# FPGA_IO.net
KiCad netlist of a schematic drawn in Altium Designer
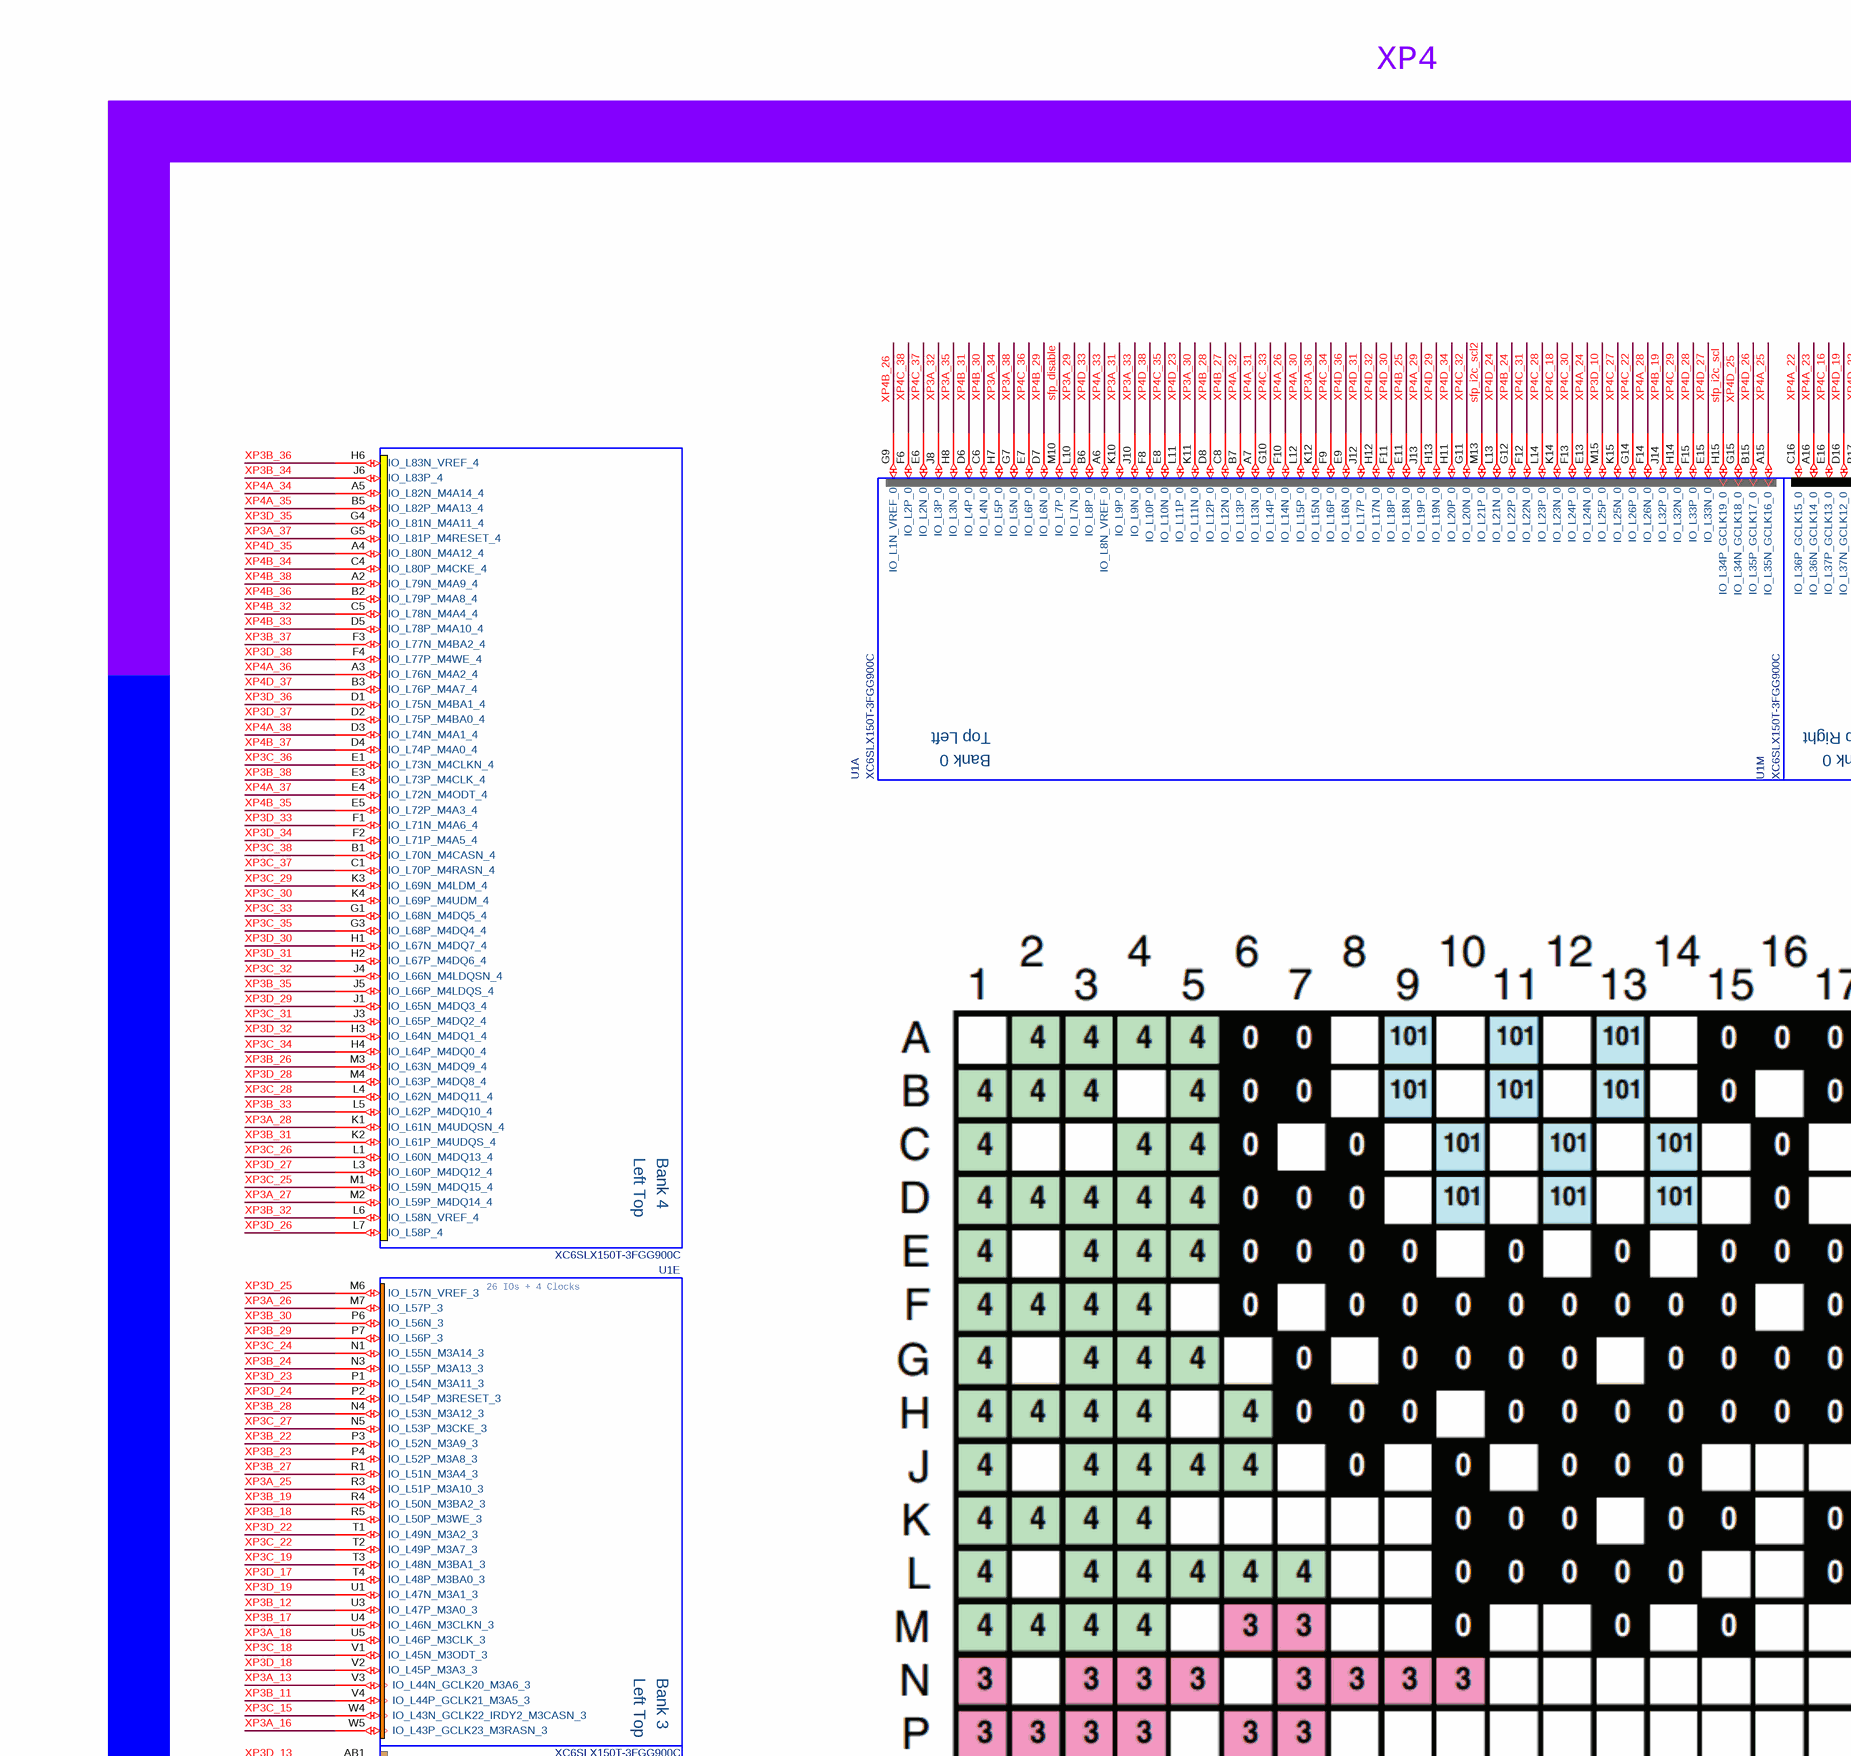
[diagram p0: FPGA_IO.SchDoc, top left]
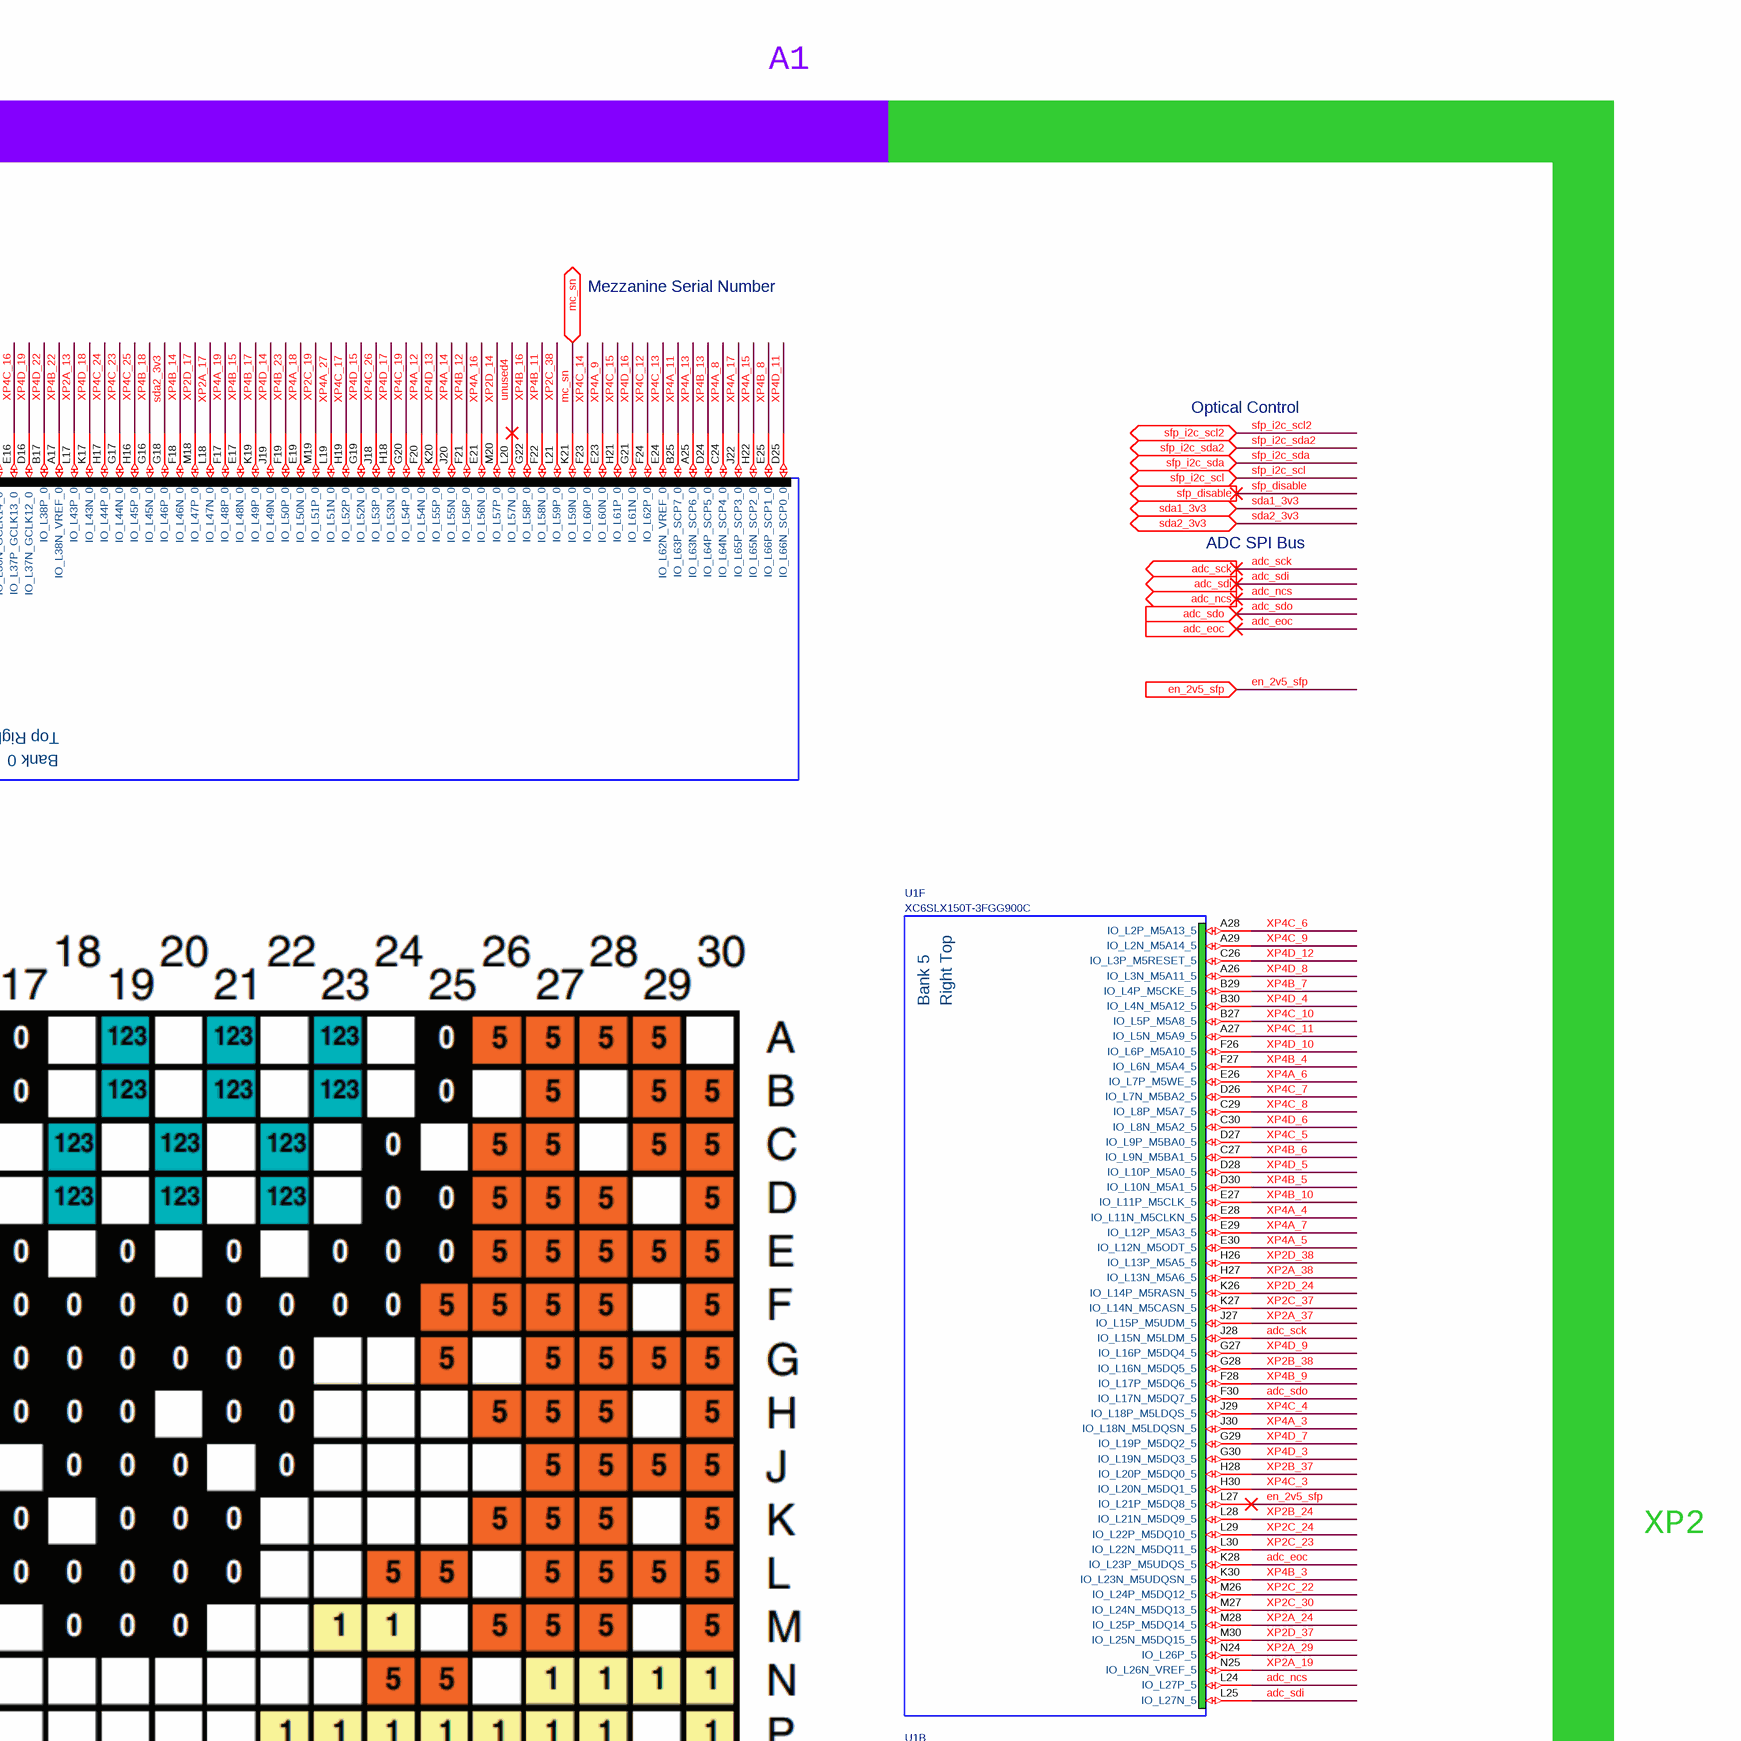
[diagram p1: FPGA_IO.SchDoc, top right]
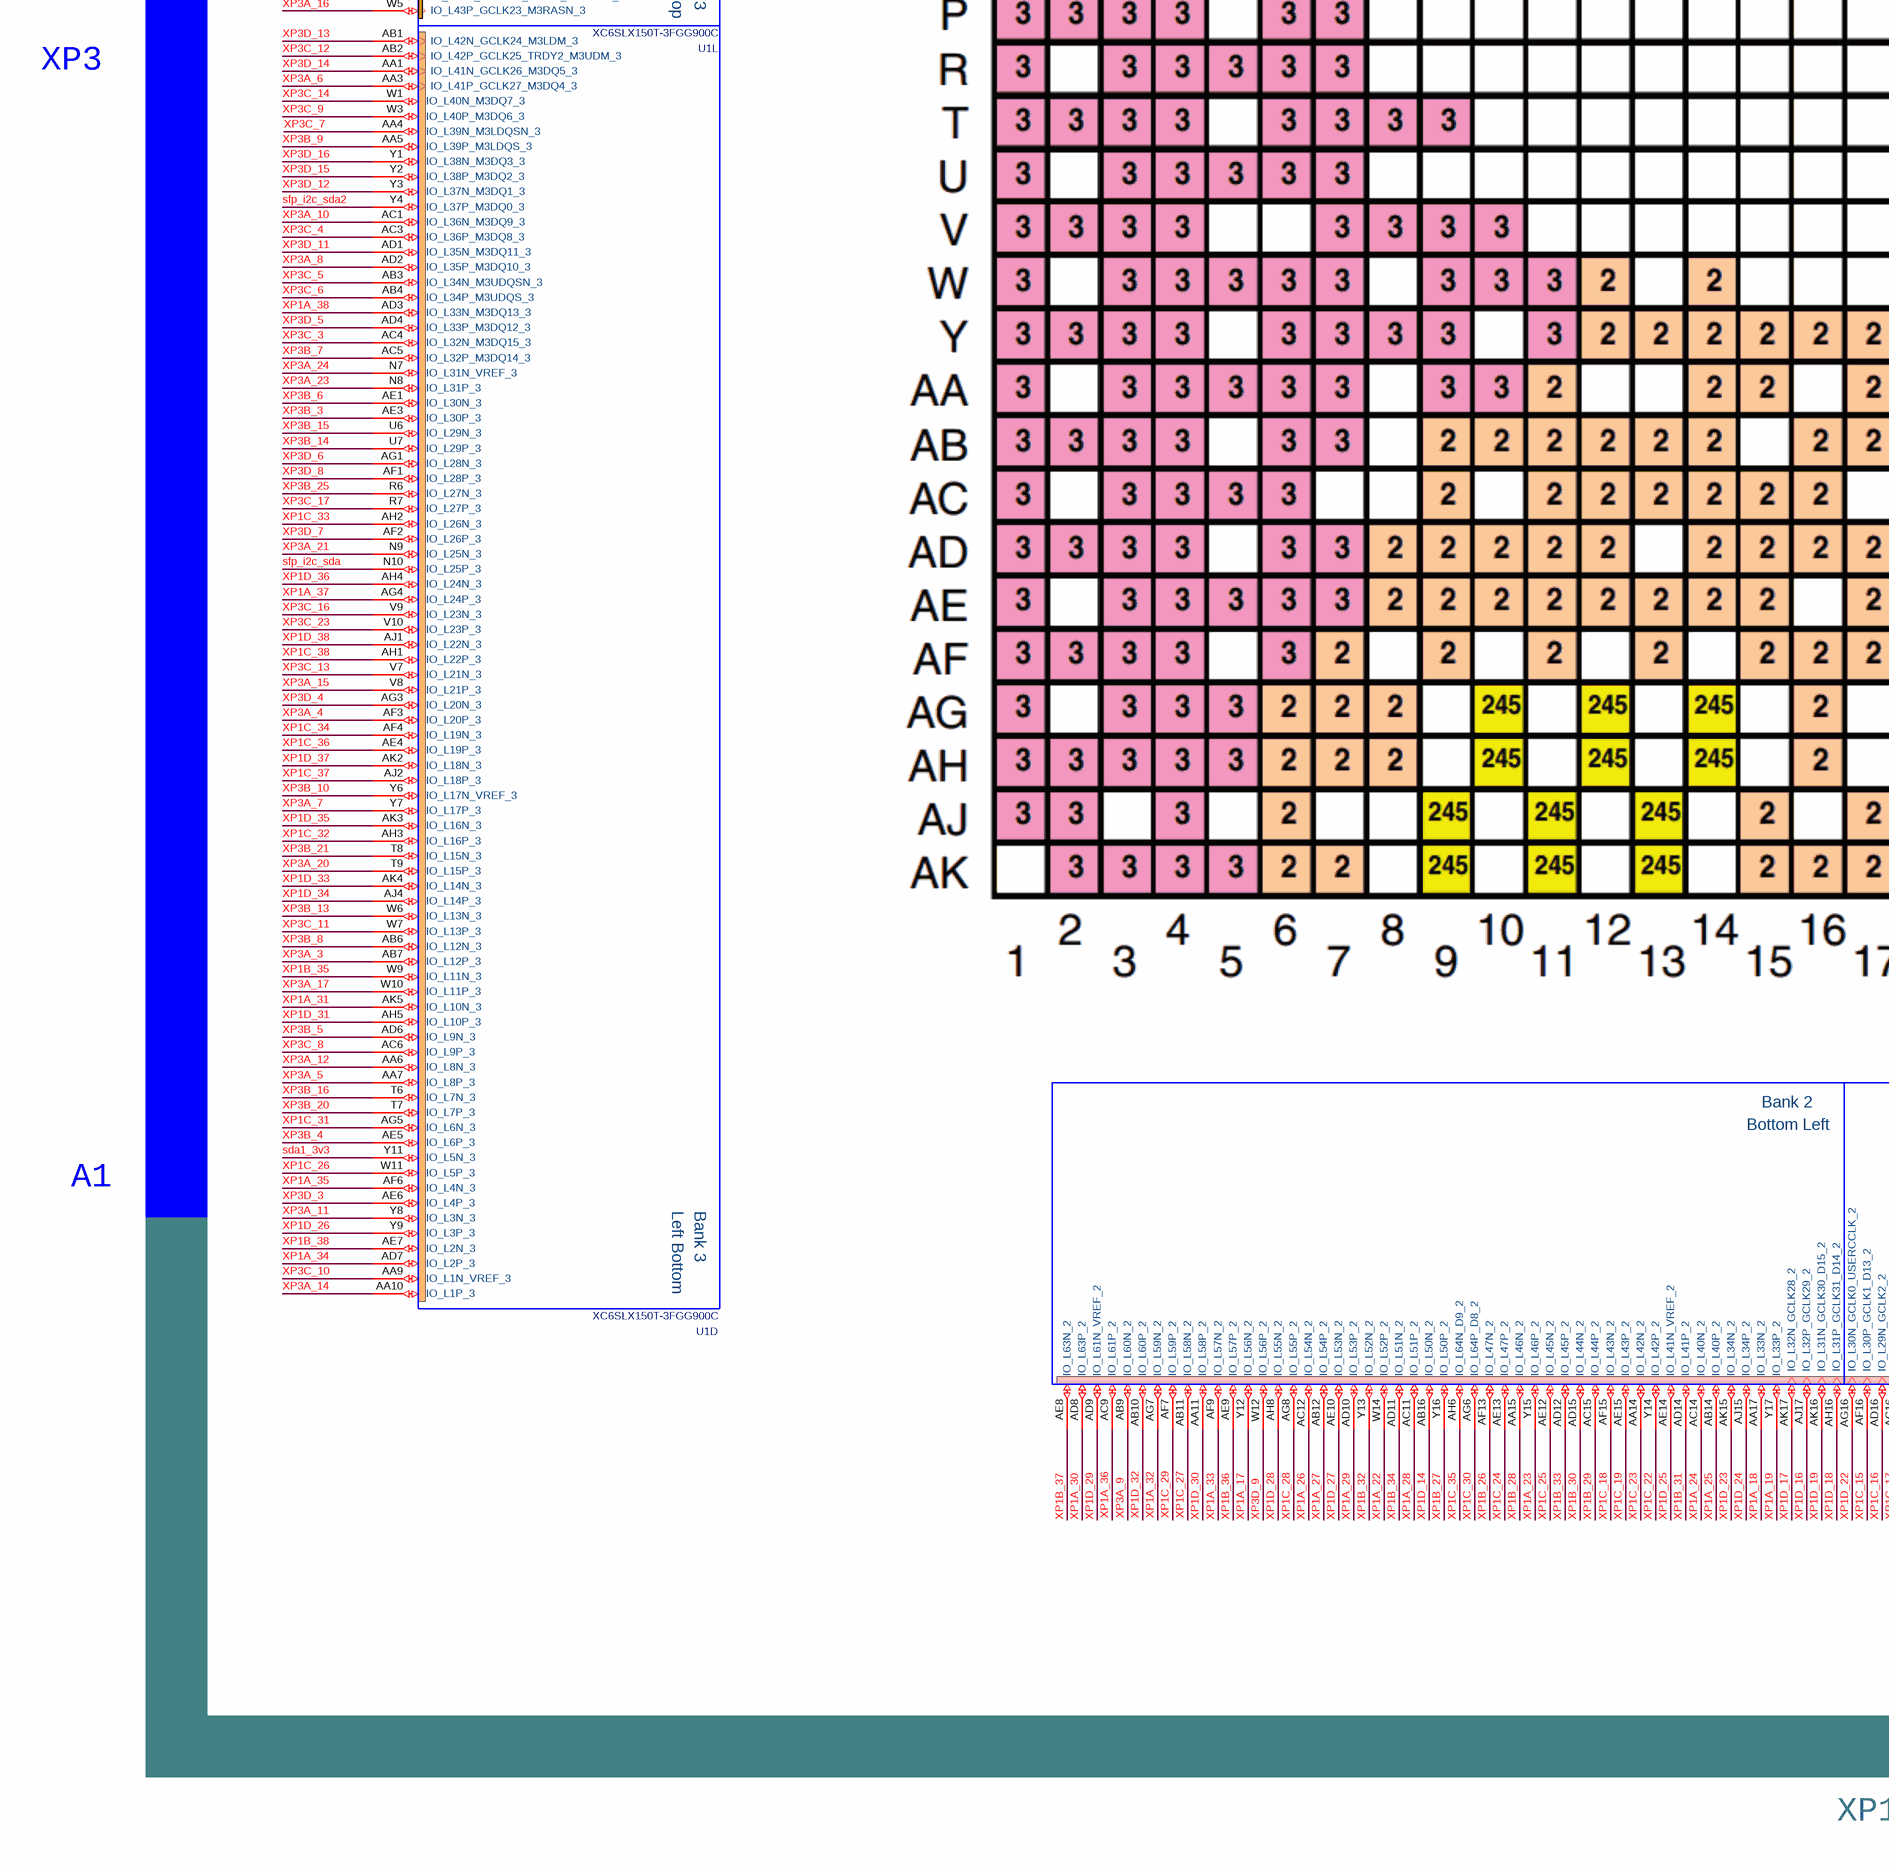
[diagram p2: FPGA_IO.SchDoc, bottom left]
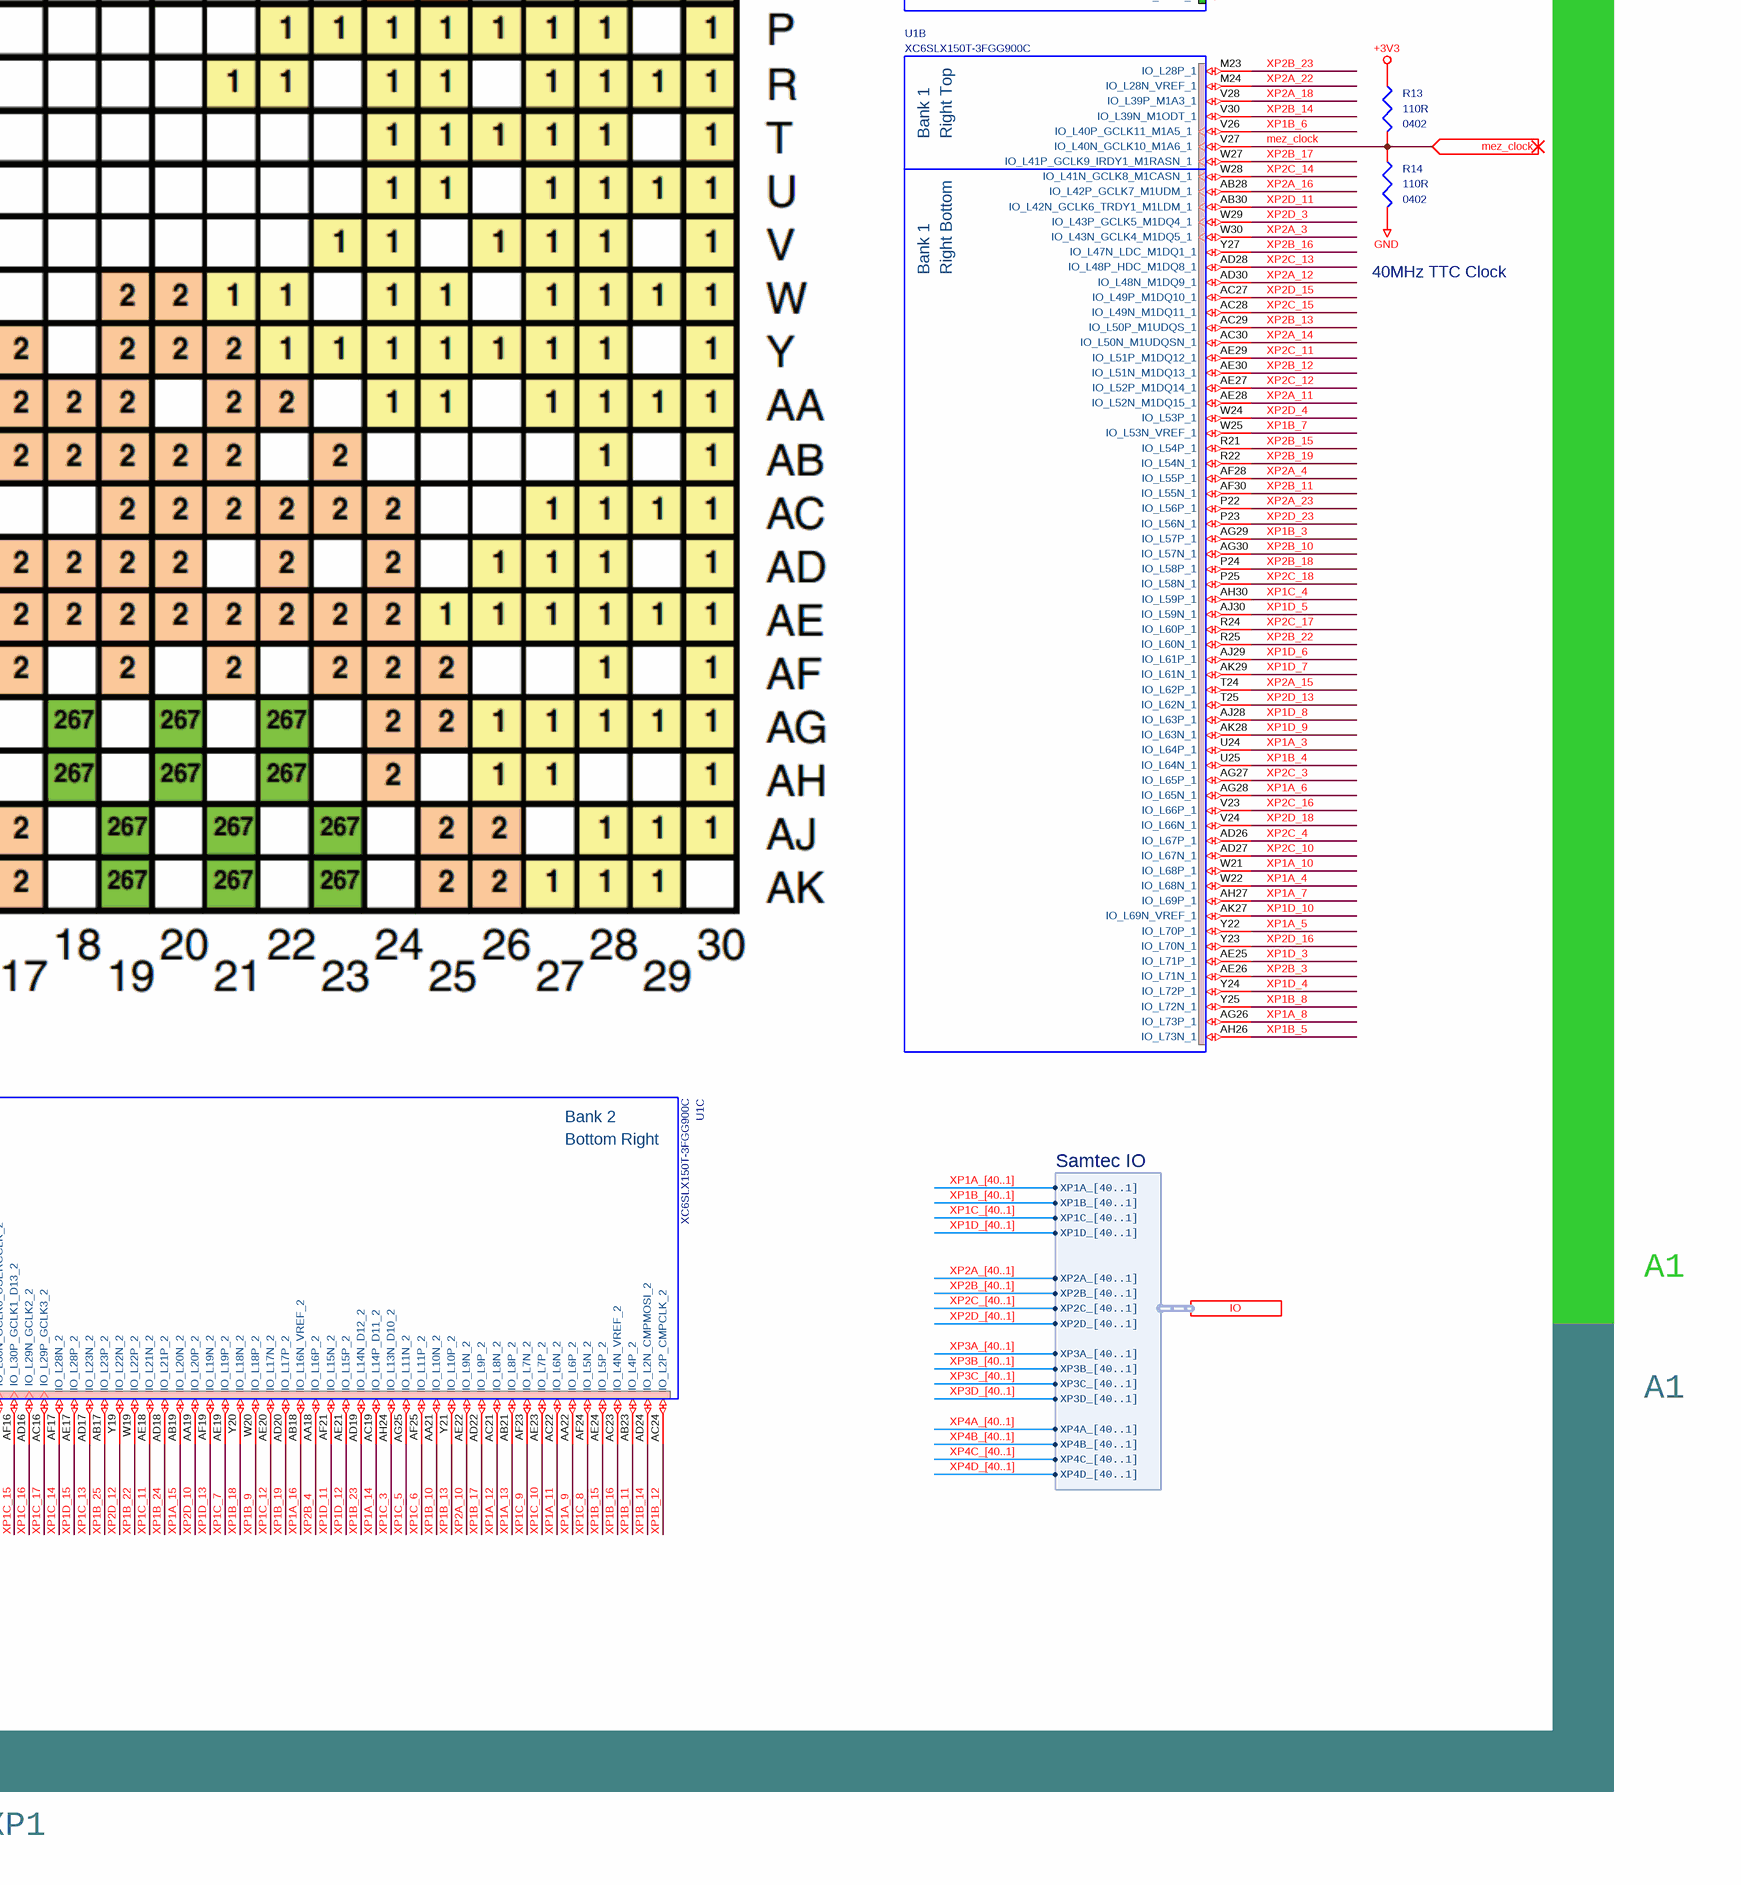
[diagram p3: FPGA_IO.SchDoc, bottom right]

(export (version "E")
  (design (tool "Eeschema 10.0.6"))
  (components
    (comp (ref "R13")
      (value "110R")
      (footprint "MC_S6/SM/R_0402_IPC")
      (description "RES SMD 110 OHM 1% 1/10W 0402")
      (fields
        (field (name "MANUFACTURER") "Panasonic Electronic Components")
        (field (name "MANUFACTURER PART NUMBER") "ERJ-2RKF1100X")
        (field (name "SUPPLIER DEVICE PACKAGE") "0402")
      )
      (libsource (lib "ALCT_MEZ_SPARTAN6_Library") (part "ERJ-2RKF1100X"))
    )
    (comp (ref "R14")
      (value "110R")
      (footprint "MC_S6/SM/R_0402_IPC")
      (description "RES SMD 110 OHM 1% 1/10W 0402")
      (fields
        (field (name "MANUFACTURER") "Panasonic Electronic Components")
        (field (name "MANUFACTURER PART NUMBER") "ERJ-2RKF1100X")
        (field (name "SUPPLIER DEVICE PACKAGE") "0402")
      )
      (libsource (lib "ALCT_MEZ_SPARTAN6_Library") (part "ERJ-2RKF1100X"))
    )
    (comp (ref "U1")
      (value "XC6SLX150T-3FGG900C")
      (footprint "MC_S6/BGA/FGG900")
      (fields (field (name "MANUFACTURER") "Xilinx Inc."))
      (libsource (lib "") (part "XC6SLX150T-3FGG900C_2"))
    )
  )
  (nets
    (net (code "160") (name "+3V3") (class "Default")
      (node (ref "R13") (pin "1") (pinfunction "1_1") (pintype "passive"))
    )
    (net (code "162") (name "/XP1A_3") (class "Default")
      (node (ref "U1") (pin "U24") (pinfunction "IO_L64P_1_U24") (pintype "bidirectional"))
    )
    (net (code "163") (name "/XP1A_4") (class "Default")
      (node (ref "U1") (pin "W22") (pinfunction "IO_L68N_1_W22") (pintype "bidirectional"))
    )
    (net (code "164") (name "/XP1A_5") (class "Default")
      (node (ref "U1") (pin "Y22") (pinfunction "IO_L70P_1_Y22") (pintype "bidirectional"))
    )
    (net (code "165") (name "/XP1A_6") (class "Default")
      (node (ref "U1") (pin "AG28") (pinfunction "IO_L65N_1_AG28") (pintype "bidirectional"))
    )
    (net (code "166") (name "/XP1A_7") (class "Default")
      (node (ref "U1") (pin "AH27") (pinfunction "IO_L69P_1_AH27") (pintype "bidirectional"))
    )
    (net (code "167") (name "/XP1A_8") (class "Default")
      (node (ref "U1") (pin "AG26") (pinfunction "IO_L73P_1_AG26") (pintype "bidirectional"))
    )
    (net (code "168") (name "/XP1A_9") (class "Default")
      (node (ref "U1") (pin "AA22") (pinfunction "IO_L6P_2_AA22") (pintype "bidirectional"))
    )
    (net (code "169") (name "/XP1A_10") (class "Default")
      (node (ref "U1") (pin "W21") (pinfunction "IO_L68P_1_W21") (pintype "bidirectional"))
    )
    (net (code "170") (name "/XP1A_11") (class "Default")
      (node (ref "U1") (pin "AC22") (pinfunction "IO_L6N_2_AC22") (pintype "bidirectional"))
    )
    (net (code "171") (name "/XP1A_12") (class "Default")
      (node (ref "U1") (pin "AC21") (pinfunction "IO_L8N_2_AC21") (pintype "bidirectional"))
    )
    (net (code "172") (name "/XP1A_13") (class "Default")
      (node (ref "U1") (pin "AB21") (pinfunction "IO_L8P_2_AB21") (pintype "bidirectional"))
    )
    (net (code "173") (name "/XP1A_14") (class "Default")
      (node (ref "U1") (pin "AC19") (pinfunction "IO_L14P_D11_2_AC19") (pintype "bidirectional"))
    )
    (net (code "174") (name "/XP1A_15") (class "Default")
      (node (ref "U1") (pin "AB19") (pinfunction "IO_L20N_2_AB19") (pintype "bidirectional"))
    )
    (net (code "175") (name "/XP1A_16") (class "Default")
      (node (ref "U1") (pin "AB18") (pinfunction "IO_L16N_VREF_2_AB18") (pintype "bidirectional"))
    )
    (net (code "176") (name "/XP1A_17") (class "Default")
      (node (ref "U1") (pin "Y12") (pinfunction "IO_L56N_2_Y12") (pintype "bidirectional"))
    )
    (net (code "177") (name "/XP1A_18") (class "Default")
      (node (ref "U1") (pin "AA17") (pinfunction "IO_L33N_2_AA17") (pintype "bidirectional"))
    )
    (net (code "178") (name "/XP1A_19") (class "Default")
      (node (ref "U1") (pin "Y17") (pinfunction "IO_L33P_2_Y17") (pintype "bidirectional"))
    )
    (net (code "179") (name "/XP1A_22") (class "Default")
      (node (ref "U1") (pin "W14") (pinfunction "IO_L52P_2_W14") (pintype "bidirectional"))
    )
    (net (code "180") (name "/XP1A_23") (class "Default")
      (node (ref "U1") (pin "Y15") (pinfunction "IO_L46P_2_Y15") (pintype "bidirectional"))
    )
    (net (code "181") (name "/XP1A_24") (class "Default")
      (node (ref "U1") (pin "AC14") (pinfunction "IO_L40N_2_AC14") (pintype "bidirectional"))
    )
    (net (code "182") (name "/XP1A_25") (class "Default")
      (node (ref "U1") (pin "AB14") (pinfunction "IO_L40P_2_AB14") (pintype "bidirectional"))
    )
    (net (code "183") (name "/XP1A_26") (class "Default")
      (node (ref "U1") (pin "AC12") (pinfunction "IO_L54N_2_AC12") (pintype "bidirectional"))
    )
    (net (code "184") (name "/XP1A_27") (class "Default")
      (node (ref "U1") (pin "AB12") (pinfunction "IO_L54P_2_AB12") (pintype "bidirectional"))
    )
    (net (code "185") (name "/XP1A_28") (class "Default")
      (node (ref "U1") (pin "AC11") (pinfunction "IO_L51P_2_AC11") (pintype "bidirectional"))
    )
    (net (code "186") (name "/XP1A_29") (class "Default")
      (node (ref "U1") (pin "AD10") (pinfunction "IO_L53P_2_AD10") (pintype "bidirectional"))
    )
    (net (code "187") (name "/XP1A_30") (class "Default")
      (node (ref "U1") (pin "AD8") (pinfunction "IO_L63P_2_AD8") (pintype "bidirectional"))
    )
    (net (code "188") (name "/XP1A_31") (class "Default")
      (node (ref "U1") (pin "AK5") (pinfunction "IO_L10N_3_AK5") (pintype "bidirectional"))
    )
    (net (code "189") (name "/XP1A_32") (class "Default")
      (node (ref "U1") (pin "AG7") (pinfunction "IO_L59N_2_AG7") (pintype "bidirectional"))
    )
    (net (code "190") (name "/XP1A_33") (class "Default")
      (node (ref "U1") (pin "AF9") (pinfunction "IO_L57N_2_AF9") (pintype "bidirectional"))
    )
    (net (code "191") (name "/XP1A_34") (class "Default")
      (node (ref "U1") (pin "AD7") (pinfunction "IO_L2P_3_AD7") (pintype "bidirectional"))
    )
    (net (code "192") (name "/XP1A_35") (class "Default")
      (node (ref "U1") (pin "AF6") (pinfunction "IO_L4N_3_AF6") (pintype "bidirectional"))
    )
    (net (code "193") (name "/XP1A_36") (class "Default")
      (node (ref "U1") (pin "AC9") (pinfunction "IO_L61P_2_AC9") (pintype "bidirectional"))
    )
    (net (code "194") (name "/XP1A_37") (class "Default")
      (node (ref "U1") (pin "AG4") (pinfunction "IO_L24P_3_AG4") (pintype "bidirectional"))
    )
    (net (code "195") (name "/XP1A_38") (class "Default")
      (node (ref "U1") (pin "AD3") (pinfunction "IO_L33N_M3DQ13_3_AD3") (pintype "bidirectional"))
    )
    (net (code "197") (name "/XP1B_3") (class "Default")
      (node (ref "U1") (pin "AG29") (pinfunction "IO_L57P_1_AG29") (pintype "bidirectional"))
    )
    (net (code "198") (name "/XP1B_4") (class "Default")
      (node (ref "U1") (pin "U25") (pinfunction "IO_L64N_1_U25") (pintype "bidirectional"))
    )
    (net (code "199") (name "/XP1B_5") (class "Default")
      (node (ref "U1") (pin "AH26") (pinfunction "IO_L73N_1_AH26") (pintype "bidirectional"))
    )
    (net (code "200") (name "/XP1B_6") (class "Default")
      (node (ref "U1") (pin "V26") (pinfunction "IO_L40P_GCLK11_M1A5_1_V26") (pintype "bidirectional"))
    )
    (net (code "201") (name "/XP1B_7") (class "Default")
      (node (ref "U1") (pin "W25") (pinfunction "IO_L53N_VREF_1_W25") (pintype "bidirectional"))
    )
    (net (code "202") (name "/XP1B_8") (class "Default")
      (node (ref "U1") (pin "Y25") (pinfunction "IO_L72N_1_Y25") (pintype "bidirectional"))
    )
    (net (code "203") (name "/XP1B_9") (class "Default")
      (node (ref "U1") (pin "W20") (pinfunction "IO_L18P_2_W20") (pintype "bidirectional"))
    )
    (net (code "204") (name "/XP1B_10") (class "Default")
      (node (ref "U1") (pin "AA21") (pinfunction "IO_L10N_2_AA21") (pintype "bidirectional"))
    )
    (net (code "205") (name "/XP1B_11") (class "Default")
      (node (ref "U1") (pin "AB23") (pinfunction "IO_L4P_2_AB23") (pintype "bidirectional"))
    )
    (net (code "206") (name "/XP1B_12") (class "Default")
      (node (ref "U1") (pin "AC24") (pinfunction "IO_L2P_CMPCLK_2_AC24") (pintype "bidirectional"))
    )
    (net (code "207") (name "/XP1B_13") (class "Default")
      (node (ref "U1") (pin "Y21") (pinfunction "IO_L10P_2_Y21") (pintype "bidirectional"))
    )
    (net (code "208") (name "/XP1B_14") (class "Default")
      (node (ref "U1") (pin "AD24") (pinfunction "IO_L2N_CMPMOSI_2_AD24") (pintype "bidirectional"))
    )
    (net (code "209") (name "/XP1B_15") (class "Default")
      (node (ref "U1") (pin "AE24") (pinfunction "IO_L5P_2_AE24") (pintype "bidirectional"))
    )
    (net (code "210") (name "/XP1B_16") (class "Default")
      (node (ref "U1") (pin "AC23") (pinfunction "IO_L4N_VREF_2_AC23") (pintype "bidirectional"))
    )
    (net (code "211") (name "/XP1B_17") (class "Default")
      (node (ref "U1") (pin "AD22") (pinfunction "IO_L9P_2_AD22") (pintype "bidirectional"))
    )
    (net (code "212") (name "/XP1B_18") (class "Default")
      (node (ref "U1") (pin "Y20") (pinfunction "IO_L18N_2_Y20") (pintype "bidirectional"))
    )
    (net (code "213") (name "/XP1B_19") (class "Default")
      (node (ref "U1") (pin "AD20") (pinfunction "IO_L17P_2_AD20") (pintype "bidirectional"))
    )
    (net (code "214") (name "/XP1B_22") (class "Default")
      (node (ref "U1") (pin "W19") (pinfunction "IO_L22P_2_W19") (pintype "bidirectional"))
    )
    (net (code "215") (name "/XP1B_23") (class "Default")
      (node (ref "U1") (pin "AD19") (pinfunction "IO_L14N_D12_2_AD19") (pintype "bidirectional"))
    )
    (net (code "216") (name "/XP1B_24") (class "Default")
      (node (ref "U1") (pin "AD18") (pinfunction "IO_L21P_2_AD18") (pintype "bidirectional"))
    )
    (net (code "217") (name "/XP1B_25") (class "Default")
      (node (ref "U1") (pin "AB17") (pinfunction "IO_L23P_2_AB17") (pintype "bidirectional"))
    )
    (net (code "218") (name "/XP1B_26") (class "Default")
      (node (ref "U1") (pin "AF13") (pinfunction "IO_L47N_2_AF13") (pintype "bidirectional"))
    )
    (net (code "219") (name "/XP1B_27") (class "Default")
      (node (ref "U1") (pin "Y16") (pinfunction "IO_L50P_2_Y16") (pintype "bidirectional"))
    )
    (net (code "220") (name "/XP1B_28") (class "Default")
      (node (ref "U1") (pin "AA15") (pinfunction "IO_L46N_2_AA15") (pintype "bidirectional"))
    )
    (net (code "221") (name "/XP1B_29") (class "Default")
      (node (ref "U1") (pin "AC15") (pinfunction "IO_L44P_2_AC15") (pintype "bidirectional"))
    )
    (net (code "222") (name "/XP1B_30") (class "Default")
      (node (ref "U1") (pin "AD15") (pinfunction "IO_L44N_2_AD15") (pintype "bidirectional"))
    )
    (net (code "223") (name "/XP1B_31") (class "Default")
      (node (ref "U1") (pin "AD14") (pinfunction "IO_L41P_2_AD14") (pintype "bidirectional"))
    )
    (net (code "224") (name "/XP1B_32") (class "Default")
      (node (ref "U1") (pin "Y13") (pinfunction "IO_L52N_2_Y13") (pintype "bidirectional"))
    )
    (net (code "225") (name "/XP1B_33") (class "Default")
      (node (ref "U1") (pin "AD12") (pinfunction "IO_L45P_2_AD12") (pintype "bidirectional"))
    )
    (net (code "226") (name "/XP1B_34") (class "Default")
      (node (ref "U1") (pin "AD11") (pinfunction "IO_L51N_2_AD11") (pintype "bidirectional"))
    )
    (net (code "227") (name "/XP1B_35") (class "Default")
      (node (ref "U1") (pin "W9") (pinfunction "IO_L11N_3_W9") (pintype "bidirectional"))
    )
    (net (code "228") (name "/XP1B_36") (class "Default")
      (node (ref "U1") (pin "AE9") (pinfunction "IO_L57P_2_AE9") (pintype "bidirectional"))
    )
    (net (code "229") (name "/XP1B_37") (class "Default")
      (node (ref "U1") (pin "AE8") (pinfunction "IO_L63N_2_AE8") (pintype "bidirectional"))
    )
    (net (code "230") (name "/XP1B_38") (class "Default")
      (node (ref "U1") (pin "AE7") (pinfunction "IO_L2N_3_AE7") (pintype "bidirectional"))
    )
    (net (code "232") (name "/XP1C_3") (class "Default")
      (node (ref "U1") (pin "AH24") (pinfunction "IO_L13N_D10_2_AH24") (pintype "bidirectional"))
    )
    (net (code "233") (name "/XP1C_4") (class "Default")
      (node (ref "U1") (pin "AH30") (pinfunction "IO_L59P_1_AH30") (pintype "bidirectional"))
    )
    (net (code "234") (name "/XP1C_5") (class "Default")
      (node (ref "U1") (pin "AG25") (pinfunction "IO_L11N_2_AG25") (pintype "bidirectional"))
    )
    (net (code "235") (name "/XP1C_6") (class "Default")
      (node (ref "U1") (pin "AF25") (pinfunction "IO_L11P_2_AF25") (pintype "bidirectional"))
    )
    (net (code "236") (name "/XP1C_7") (class "Default")
      (node (ref "U1") (pin "AE19") (pinfunction "IO_L19P_2_AE19") (pintype "bidirectional"))
    )
    (net (code "237") (name "/XP1C_8") (class "Default")
      (node (ref "U1") (pin "AF24") (pinfunction "IO_L5N_2_AF24") (pintype "bidirectional"))
    )
    (net (code "238") (name "/XP1C_9") (class "Default")
      (node (ref "U1") (pin "AF23") (pinfunction "IO_L7N_2_AF23") (pintype "bidirectional"))
    )
    (net (code "239") (name "/XP1C_10") (class "Default")
      (node (ref "U1") (pin "AE23") (pinfunction "IO_L7P_2_AE23") (pintype "bidirectional"))
    )
    (net (code "240") (name "/XP1C_11") (class "Default")
      (node (ref "U1") (pin "AE18") (pinfunction "IO_L21N_2_AE18") (pintype "bidirectional"))
    )
    (net (code "241") (name "/XP1C_12") (class "Default")
      (node (ref "U1") (pin "AE20") (pinfunction "IO_L17N_2_AE20") (pintype "bidirectional"))
    )
    (net (code "242") (name "/XP1C_13") (class "Default")
      (node (ref "U1") (pin "AD17") (pinfunction "IO_L23N_2_AD17") (pintype "bidirectional"))
    )
    (net (code "243") (name "/XP1C_14") (class "Default")
      (node (ref "U1") (pin "AF17") (pinfunction "IO_L28N_2_AF17") (pintype "bidirectional"))
    )
    (net (code "244") (name "/XP1C_15") (class "Default")
      (node (ref "U1") (pin "AF16") (pinfunction "IO_L30P_GCLK1_D13_2_AF16") (pintype "bidirectional"))
    )
    (net (code "245") (name "/XP1C_16") (class "Default")
      (node (ref "U1") (pin "AD16") (pinfunction "IO_L29N_GCLK2_2_AD16") (pintype "bidirectional"))
    )
    (net (code "246") (name "/XP1C_17") (class "Default")
      (node (ref "U1") (pin "AC16") (pinfunction "IO_L29P_GCLK3_2_AC16") (pintype "bidirectional"))
    )
    (net (code "247") (name "/XP1C_18") (class "Default")
      (node (ref "U1") (pin "AF15") (pinfunction "IO_L43N_2_AF15") (pintype "bidirectional"))
    )
    (net (code "248") (name "/XP1C_19") (class "Default")
      (node (ref "U1") (pin "AE15") (pinfunction "IO_L43P_2_AE15") (pintype "bidirectional"))
    )
    (net (code "249") (name "/XP1C_22") (class "Default")
      (node (ref "U1") (pin "Y14") (pinfunction "IO_L42P_2_Y14") (pintype "bidirectional"))
    )
    (net (code "250") (name "/XP1C_23") (class "Default")
      (node (ref "U1") (pin "AA14") (pinfunction "IO_L42N_2_AA14") (pintype "bidirectional"))
    )
    (net (code "251") (name "/XP1C_24") (class "Default")
      (node (ref "U1") (pin "AE13") (pinfunction "IO_L47P_2_AE13") (pintype "bidirectional"))
    )
    (net (code "252") (name "/XP1C_25") (class "Default")
      (node (ref "U1") (pin "AE12") (pinfunction "IO_L45N_2_AE12") (pintype "bidirectional"))
    )
    (net (code "253") (name "/XP1C_26") (class "Default")
      (node (ref "U1") (pin "W11") (pinfunction "IO_L5P_3_W11") (pintype "bidirectional"))
    )
    (net (code "254") (name "/XP1C_27") (class "Default")
      (node (ref "U1") (pin "AB11") (pinfunction "IO_L58N_2_AB11") (pintype "bidirectional"))
    )
    (net (code "255") (name "/XP1C_28") (class "Default")
      (node (ref "U1") (pin "AG8") (pinfunction "IO_L55P_2_AG8") (pintype "bidirectional"))
    )
    (net (code "256") (name "/XP1C_29") (class "Default")
      (node (ref "U1") (pin "AF7") (pinfunction "IO_L59P_2_AF7") (pintype "bidirectional"))
    )
    (net (code "257") (name "/XP1C_30") (class "Default")
      (node (ref "U1") (pin "AG6") (pinfunction "IO_L64P_D8_2_AG6") (pintype "bidirectional"))
    )
    (net (code "258") (name "/XP1C_31") (class "Default")
      (node (ref "U1") (pin "AG5") (pinfunction "IO_L6N_3_AG5") (pintype "bidirectional"))
    )
    (net (code "259") (name "/XP1C_32") (class "Default")
      (node (ref "U1") (pin "AH3") (pinfunction "IO_L16P_3_AH3") (pintype "bidirectional"))
    )
    (net (code "260") (name "/XP1C_33") (class "Default")
      (node (ref "U1") (pin "AH2") (pinfunction "IO_L26N_3_AH2") (pintype "bidirectional"))
    )
    (net (code "261") (name "/XP1C_34") (class "Default")
      (node (ref "U1") (pin "AF4") (pinfunction "IO_L19N_3_AF4") (pintype "bidirectional"))
    )
    (net (code "262") (name "/XP1C_35") (class "Default")
      (node (ref "U1") (pin "AH6") (pinfunction "IO_L64N_D9_2_AH6") (pintype "bidirectional"))
    )
    (net (code "263") (name "/XP1C_36") (class "Default")
      (node (ref "U1") (pin "AE4") (pinfunction "IO_L19P_3_AE4") (pintype "bidirectional"))
    )
    (net (code "264") (name "/XP1C_37") (class "Default")
      (node (ref "U1") (pin "AJ2") (pinfunction "IO_L18P_3_AJ2") (pintype "bidirectional"))
    )
    (net (code "265") (name "/XP1C_38") (class "Default")
      (node (ref "U1") (pin "AH1") (pinfunction "IO_L22P_3_AH1") (pintype "bidirectional"))
    )
    (net (code "267") (name "/XP1D_3") (class "Default")
      (node (ref "U1") (pin "AE25") (pinfunction "IO_L71P_1_AE25") (pintype "bidirectional"))
    )
    (net (code "268") (name "/XP1D_4") (class "Default")
      (node (ref "U1") (pin "Y24") (pinfunction "IO_L72P_1_Y24") (pintype "bidirectional"))
    )
    (net (code "269") (name "/XP1D_5") (class "Default")
      (node (ref "U1") (pin "AJ30") (pinfunction "IO_L59N_1_AJ30") (pintype "bidirectional"))
    )
    (net (code "270") (name "/XP1D_6") (class "Default")
      (node (ref "U1") (pin "AJ29") (pinfunction "IO_L61P_1_AJ29") (pintype "bidirectional"))
    )
    (net (code "271") (name "/XP1D_7") (class "Default")
      (node (ref "U1") (pin "AK29") (pinfunction "IO_L61N_1_AK29") (pintype "bidirectional"))
    )
    (net (code "272") (name "/XP1D_8") (class "Default")
      (node (ref "U1") (pin "AJ28") (pinfunction "IO_L63P_1_AJ28") (pintype "bidirectional"))
    )
    (net (code "273") (name "/XP1D_9") (class "Default")
      (node (ref "U1") (pin "AK28") (pinfunction "IO_L63N_1_AK28") (pintype "bidirectional"))
    )
    (net (code "274") (name "/XP1D_10") (class "Default")
      (node (ref "U1") (pin "AK27") (pinfunction "IO_L69N_VREF_1_AK27") (pintype "bidirectional"))
    )
    (net (code "275") (name "/XP1D_11") (class "Default")
      (node (ref "U1") (pin "AF21") (pinfunction "IO_L15N_2_AF21") (pintype "bidirectional"))
    )
    (net (code "276") (name "/XP1D_12") (class "Default")
      (node (ref "U1") (pin "AE21") (pinfunction "IO_L15P_2_AE21") (pintype "bidirectional"))
    )
    (net (code "277") (name "/XP1D_13") (class "Default")
      (node (ref "U1") (pin "AF19") (pinfunction "IO_L19N_2_AF19") (pintype "bidirectional"))
    )
    (net (code "278") (name "/XP1D_14") (class "Default")
      (node (ref "U1") (pin "AB16") (pinfunction "IO_L50N_2_AB16") (pintype "bidirectional"))
    )
    (net (code "279") (name "/XP1D_15") (class "Default")
      (node (ref "U1") (pin "AE17") (pinfunction "IO_L28P_2_AE17") (pintype "bidirectional"))
    )
    (net (code "280") (name "/XP1D_16") (class "Default")
      (node (ref "U1") (pin "AJ17") (pinfunction "IO_L32P_GCLK29_2_AJ17") (pintype "bidirectional"))
    )
    (net (code "281") (name "/XP1D_17") (class "Default")
      (node (ref "U1") (pin "AK17") (pinfunction "IO_L32N_GCLK28_2_AK17") (pintype "bidirectional"))
    )
    (net (code "282") (name "/XP1D_18") (class "Default")
      (node (ref "U1") (pin "AH16") (pinfunction "IO_L31P_GCLK31_D14_2_AH16") (pintype "bidirectional"))
    )
    (net (code "283") (name "/XP1D_19") (class "Default")
      (node (ref "U1") (pin "AK16") (pinfunction "IO_L31N_GCLK30_D15_2_AK16") (pintype "bidirectional"))
    )
    (net (code "284") (name "/XP1D_22") (class "Default")
      (node (ref "U1") (pin "AG16") (pinfunction "IO_L30N_GCLK0_USERCCLK_2_AG16") (pintype "bidirectional"))
    )
    (net (code "285") (name "/XP1D_23") (class "Default")
      (node (ref "U1") (pin "AK15") (pinfunction "IO_L34N_2_AK15") (pintype "bidirectional"))
    )
    (net (code "286") (name "/XP1D_24") (class "Default")
      (node (ref "U1") (pin "AJ15") (pinfunction "IO_L34P_2_AJ15") (pintype "bidirectional"))
    )
    (net (code "287") (name "/XP1D_25") (class "Default")
      (node (ref "U1") (pin "AE14") (pinfunction "IO_L41N_VREF_2_AE14") (pintype "bidirectional"))
    )
    (net (code "288") (name "/XP1D_26") (class "Default")
      (node (ref "U1") (pin "Y9") (pinfunction "IO_L3P_3_Y9") (pintype "bidirectional"))
    )
    (net (code "289") (name "/XP1D_27") (class "Default")
      (node (ref "U1") (pin "AE10") (pinfunction "IO_L53N_2_AE10") (pintype "bidirectional"))
    )
    (net (code "290") (name "/XP1D_28") (class "Default")
      (node (ref "U1") (pin "AH8") (pinfunction "IO_L55N_2_AH8") (pintype "bidirectional"))
    )
    (net (code "291") (name "/XP1D_29") (class "Default")
      (node (ref "U1") (pin "AD9") (pinfunction "IO_L61N_VREF_2_AD9") (pintype "bidirectional"))
    )
    (net (code "292") (name "/XP1D_30") (class "Default")
      (node (ref "U1") (pin "AA11") (pinfunction "IO_L58P_2_AA11") (pintype "bidirectional"))
    )
    (net (code "293") (name "/XP1D_31") (class "Default")
      (node (ref "U1") (pin "AH5") (pinfunction "IO_L10P_3_AH5") (pintype "bidirectional"))
    )
    (net (code "294") (name "/XP1D_32") (class "Default")
      (node (ref "U1") (pin "AB10") (pinfunction "IO_L60P_2_AB10") (pintype "bidirectional"))
    )
    (net (code "295") (name "/XP1D_33") (class "Default")
      (node (ref "U1") (pin "AK4") (pinfunction "IO_L14N_3_AK4") (pintype "bidirectional"))
    )
    (net (code "296") (name "/XP1D_34") (class "Default")
      (node (ref "U1") (pin "AJ4") (pinfunction "IO_L14P_3_AJ4") (pintype "bidirectional"))
    )
    (net (code "297") (name "/XP1D_35") (class "Default")
      (node (ref "U1") (pin "AK3") (pinfunction "IO_L16N_3_AK3") (pintype "bidirectional"))
    )
    (net (code "298") (name "/XP1D_36") (class "Default")
      (node (ref "U1") (pin "AH4") (pinfunction "IO_L24N_3_AH4") (pintype "bidirectional"))
    )
    (net (code "299") (name "/XP1D_37") (class "Default")
      (node (ref "U1") (pin "AK2") (pinfunction "IO_L18N_3_AK2") (pintype "bidirectional"))
    )
    (net (code "300") (name "/XP1D_38") (class "Default")
      (node (ref "U1") (pin "AJ1") (pinfunction "IO_L22N_3_AJ1") (pintype "bidirectional"))
    )
    (net (code "302") (name "/XP2A_3") (class "Default")
      (node (ref "U1") (pin "W30") (pinfunction "IO_L43N_GCLK4_M1DQ5_1_W30") (pintype "bidirectional"))
    )
    (net (code "303") (name "/XP2A_4") (class "Default")
      (node (ref "U1") (pin "AF28") (pinfunction "IO_L55P_1_AF28") (pintype "bidirectional"))
    )
    (net (code "304") (name "/XP2A_10") (class "Default")
      (node (ref "U1") (pin "AE22") (pinfunction "IO_L9N_2_AE22") (pintype "bidirectional"))
    )
    (net (code "305") (name "/XP2A_11") (class "Default")
      (node (ref "U1") (pin "AE28") (pinfunction "IO_L52N_M1DQ15_1_AE28") (pintype "bidirectional"))
    )
    (net (code "306") (name "/XP2A_12") (class "Default")
      (node (ref "U1") (pin "AD30") (pinfunction "IO_L48N_M1DQ9_1_AD30") (pintype "bidirectional"))
    )
    (net (code "307") (name "/XP2A_13") (class "Default")
      (node (ref "U1") (pin "L17") (pinfunction "IO_L43P_0_L17") (pintype "bidirectional"))
    )
    (net (code "308") (name "/XP2A_14") (class "Default")
      (node (ref "U1") (pin "AC30") (pinfunction "IO_L50N_M1UDQSN_1_AC30") (pintype "bidirectional"))
    )
    (net (code "309") (name "/XP2A_15") (class "Default")
      (node (ref "U1") (pin "T24") (pinfunction "IO_L62P_1_T24") (pintype "bidirectional"))
    )
    (net (code "310") (name "/XP2A_16") (class "Default")
      (node (ref "U1") (pin "AB28") (pinfunction "IO_L42P_GCLK7_M1UDM_1_AB28") (pintype "bidirectional"))
    )
    (net (code "311") (name "/XP2A_17") (class "Default")
      (node (ref "U1") (pin "L18") (pinfunction "IO_L47N_0_L18") (pintype "bidirectional"))
    )
    (net (code "312") (name "/XP2A_18") (class "Default")
      (node (ref "U1") (pin "V28") (pinfunction "IO_L39P_M1A3_1_V28") (pintype "bidirectional"))
    )
    (net (code "313") (name "/XP2A_19") (class "Default")
      (node (ref "U1") (pin "N25") (pinfunction "IO_L26N_VREF_5_N25") (pintype "bidirectional"))
    )
    (net (code "314") (name "/XP2A_22") (class "Default")
      (node (ref "U1") (pin "M24") (pinfunction "IO_L28N_VREF_1_M24") (pintype "bidirectional"))
    )
    (net (code "315") (name "/XP2A_23") (class "Default")
      (node (ref "U1") (pin "P22") (pinfunction "IO_L56P_1_P22") (pintype "bidirectional"))
    )
    (net (code "316") (name "/XP2A_24") (class "Default")
      (node (ref "U1") (pin "M28") (pinfunction "IO_L25P_M5DQ14_5_M28") (pintype "bidirectional"))
    )
    (net (code "317") (name "/XP2A_29") (class "Default")
      (node (ref "U1") (pin "N24") (pinfunction "IO_L26P_5_N24") (pintype "bidirectional"))
    )
    (net (code "318") (name "/XP2A_37") (class "Default")
      (node (ref "U1") (pin "J27") (pinfunction "IO_L15P_M5UDM_5_J27") (pintype "bidirectional"))
    )
    (net (code "319") (name "/XP2A_38") (class "Default")
      (node (ref "U1") (pin "H27") (pinfunction "IO_L13N_M5A6_5_H27") (pintype "bidirectional"))
    )
    (net (code "321") (name "/XP2B_3") (class "Default")
      (node (ref "U1") (pin "AE26") (pinfunction "IO_L71N_1_AE26") (pintype "bidirectional"))
    )
    (net (code "322") (name "/XP2B_4") (class "Default")
      (node (ref "U1") (pin "AA18") (pinfunction "IO_L16P_2_AA18") (pintype "bidirectional"))
    )
    (net (code "323") (name "/XP2B_10") (class "Default")
      (node (ref "U1") (pin "AG30") (pinfunction "IO_L57N_1_AG30") (pintype "bidirectional"))
    )
    (net (code "324") (name "/XP2B_11") (class "Default")
      (node (ref "U1") (pin "AF30") (pinfunction "IO_L55N_1_AF30") (pintype "bidirectional"))
    )
    (net (code "325") (name "/XP2B_12") (class "Default")
      (node (ref "U1") (pin "AE30") (pinfunction "IO_L51N_M1DQ13_1_AE30") (pintype "bidirectional"))
    )
    (net (code "326") (name "/XP2B_13") (class "Default")
      (node (ref "U1") (pin "AC29") (pinfunction "IO_L50P_M1UDQS_1_AC29") (pintype "bidirectional"))
    )
    (net (code "327") (name "/XP2B_14") (class "Default")
      (node (ref "U1") (pin "V30") (pinfunction "IO_L39N_M1ODT_1_V30") (pintype "bidirectional"))
    )
    (net (code "328") (name "/XP2B_15") (class "Default")
      (node (ref "U1") (pin "R21") (pinfunction "IO_L54P_1_R21") (pintype "bidirectional"))
    )
    (net (code "329") (name "/XP2B_16") (class "Default")
      (node (ref "U1") (pin "Y27") (pinfunction "IO_L47N_LDC_M1DQ1_1_Y27") (pintype "bidirectional"))
    )
    (net (code "330") (name "/XP2B_17") (class "Default")
      (node (ref "U1") (pin "W27") (pinfunction "IO_L41P_GCLK9_IRDY1_M1RASN_1_W27") (pintype "bidirectional"))
    )
    (net (code "331") (name "/XP2B_18") (class "Default")
      (node (ref "U1") (pin "P24") (pinfunction "IO_L58P_1_P24") (pintype "bidirectional"))
    )
    (net (code "332") (name "/XP2B_19") (class "Default")
      (node (ref "U1") (pin "R22") (pinfunction "IO_L54N_1_R22") (pintype "bidirectional"))
    )
    (net (code "333") (name "/XP2B_22") (class "Default")
      (node (ref "U1") (pin "R25") (pinfunction "IO_L60N_1_R25") (pintype "bidirectional"))
    )
    (net (code "334") (name "/XP2B_23") (class "Default")
      (node (ref "U1") (pin "M23") (pinfunction "IO_L28P_1_M23") (pintype "bidirectional"))
    )
    (net (code "335") (name "/XP2B_24") (class "Default")
      (node (ref "U1") (pin "L28") (pinfunction "IO_L21N_M5DQ9_5_L28") (pintype "bidirectional"))
    )
    (net (code "336") (name "/XP2B_37") (class "Default")
      (node (ref "U1") (pin "H28") (pinfunction "IO_L20P_M5DQ0_5_H28") (pintype "bidirectional"))
    )
    (net (code "337") (name "/XP2B_38") (class "Default")
      (node (ref "U1") (pin "G28") (pinfunction "IO_L16N_M5DQ5_5_G28") (pintype "bidirectional"))
    )
    (net (code "339") (name "/XP2C_3") (class "Default")
      (node (ref "U1") (pin "AG27") (pinfunction "IO_L65P_1_AG27") (pintype "bidirectional"))
    )
    (net (code "340") (name "/XP2C_4") (class "Default")
      (node (ref "U1") (pin "AD26") (pinfunction "IO_L67P_1_AD26") (pintype "bidirectional"))
    )
    (net (code "341") (name "/XP2C_10") (class "Default")
      (node (ref "U1") (pin "AD27") (pinfunction "IO_L67N_1_AD27") (pintype "bidirectional"))
    )
    (net (code "342") (name "/XP2C_11") (class "Default")
      (node (ref "U1") (pin "AE29") (pinfunction "IO_L51P_M1DQ12_1_AE29") (pintype "bidirectional"))
    )
    (net (code "343") (name "/XP2C_12") (class "Default")
      (node (ref "U1") (pin "AE27") (pinfunction "IO_L52P_M1DQ14_1_AE27") (pintype "bidirectional"))
    )
    (net (code "344") (name "/XP2C_13") (class "Default")
      (node (ref "U1") (pin "AD28") (pinfunction "IO_L48P_HDC_M1DQ8_1_AD28") (pintype "bidirectional"))
    )
    (net (code "345") (name "/XP2C_14") (class "Default")
      (node (ref "U1") (pin "W28") (pinfunction "IO_L41N_GCLK8_M1CASN_1_W28") (pintype "bidirectional"))
    )
    (net (code "346") (name "/XP2C_15") (class "Default")
      (node (ref "U1") (pin "AC28") (pinfunction "IO_L49N_M1DQ11_1_AC28") (pintype "bidirectional"))
    )
    (net (code "347") (name "/XP2C_16") (class "Default")
      (node (ref "U1") (pin "V23") (pinfunction "IO_L66P_1_V23") (pintype "bidirectional"))
    )
    (net (code "348") (name "/XP2C_17") (class "Default")
      (node (ref "U1") (pin "R24") (pinfunction "IO_L60P_1_R24") (pintype "bidirectional"))
    )
    (net (code "349") (name "/XP2C_18") (class "Default")
      (node (ref "U1") (pin "P25") (pinfunction "IO_L58N_1_P25") (pintype "bidirectional"))
    )
    (net (code "350") (name "/XP2C_19") (class "Default")
      (node (ref "U1") (pin "M19") (pinfunction "IO_L51P_0_M19") (pintype "bidirectional"))
    )
    (net (code "351") (name "/XP2C_22") (class "Default")
      (node (ref "U1") (pin "M26") (pinfunction "IO_L24P_M5DQ12_5_M26") (pintype "bidirectional"))
    )
    (net (code "352") (name "/XP2C_23") (class "Default")
      (node (ref "U1") (pin "L30") (pinfunction "IO_L22N_M5DQ11_5_L30") (pintype "bidirectional"))
    )
    (net (code "353") (name "/XP2C_24") (class "Default")
      (node (ref "U1") (pin "L29") (pinfunction "IO_L22P_M5DQ10_5_L29") (pintype "bidirectional"))
    )
    (net (code "354") (name "/XP2C_30") (class "Default")
      (node (ref "U1") (pin "M27") (pinfunction "IO_L24N_M5DQ13_5_M27") (pintype "bidirectional"))
    )
    (net (code "355") (name "/XP2C_37") (class "Default")
      (node (ref "U1") (pin "K27") (pinfunction "IO_L14N_M5CASN_5_K27") (pintype "bidirectional"))
    )
    (net (code "356") (name "/XP2C_38") (class "Default")
      (node (ref "U1") (pin "L21") (pinfunction "IO_L59P_0_L21") (pintype "bidirectional"))
    )
    (net (code "358") (name "/XP2D_3") (class "Default")
      (node (ref "U1") (pin "W29") (pinfunction "IO_L43P_GCLK5_M1DQ4_1_W29") (pintype "bidirectional"))
    )
    (net (code "359") (name "/XP2D_4") (class "Default")
      (node (ref "U1") (pin "W24") (pinfunction "IO_L53P_1_W24") (pintype "bidirectional"))
    )
    (net (code "360") (name "/XP2D_10") (class "Default")
      (node (ref "U1") (pin "AA19") (pinfunction "IO_L20P_2_AA19") (pintype "bidirectional"))
    )
    (net (code "361") (name "/XP2D_11") (class "Default")
      (node (ref "U1") (pin "AB30") (pinfunction "IO_L42N_GCLK6_TRDY1_M1LDM_1_AB30") (pintype "bidirectional"))
    )
    (net (code "362") (name "/XP2D_12") (class "Default")
      (node (ref "U1") (pin "Y19") (pinfunction "IO_L22N_2_Y19") (pintype "bidirectional"))
    )
    (net (code "363") (name "/XP2D_13") (class "Default")
      (node (ref "U1") (pin "T25") (pinfunction "IO_L62N_1_T25") (pintype "bidirectional"))
    )
    (net (code "364") (name "/XP2D_14") (class "Default")
      (node (ref "U1") (pin "M20") (pinfunction "IO_L57P_0_M20") (pintype "bidirectional"))
    )
    (net (code "365") (name "/XP2D_15") (class "Default")
      (node (ref "U1") (pin "AC27") (pinfunction "IO_L49P_M1DQ10_1_AC27") (pintype "bidirectional"))
    )
    (net (code "366") (name "/XP2D_16") (class "Default")
      (node (ref "U1") (pin "Y23") (pinfunction "IO_L70N_1_Y23") (pintype "bidirectional"))
    )
    (net (code "367") (name "/XP2D_17") (class "Default")
      (node (ref "U1") (pin "M18") (pinfunction "IO_L47P_0_M18") (pintype "bidirectional"))
    )
    (net (code "368") (name "/XP2D_18") (class "Default")
      (node (ref "U1") (pin "V24") (pinfunction "IO_L66N_1_V24") (pintype "bidirectional"))
    )
    (net (code "369") (name "/XP2D_23") (class "Default")
      (node (ref "U1") (pin "P23") (pinfunction "IO_L56N_1_P23") (pintype "bidirectional"))
    )
    (net (code "370") (name "/XP2D_24") (class "Default")
      (node (ref "U1") (pin "K26") (pinfunction "IO_L14P_M5RASN_5_K26") (pintype "bidirectional"))
    )
    (net (code "371") (name "/XP2D_37") (class "Default")
      (node (ref "U1") (pin "M30") (pinfunction "IO_L25N_M5DQ15_5_M30") (pintype "bidirectional"))
    )
    (net (code "372") (name "/XP2D_38") (class "Default")
      (node (ref "U1") (pin "H26") (pinfunction "IO_L13P_M5A5_5_H26") (pintype "bidirectional"))
    )
    (net (code "374") (name "/XP3A_3") (class "Default")
      (node (ref "U1") (pin "AB7") (pinfunction "IO_L12P_3_AB7") (pintype "bidirectional"))
    )
    (net (code "375") (name "/XP3A_4") (class "Default")
      (node (ref "U1") (pin "AF3") (pinfunction "IO_L20P_3_AF3") (pintype "bidirectional"))
    )
    (net (code "376") (name "/XP3A_5") (class "Default")
      (node (ref "U1") (pin "AA7") (pinfunction "IO_L8P_3_AA7") (pintype "bidirectional"))
    )
    (net (code "377") (name "/XP3A_6") (class "Default")
      (node (ref "U1") (pin "AA3") (pinfunction "IO_L41P_GCLK27_M3DQ4_3_AA3") (pintype "bidirectional"))
    )
    (net (code "378") (name "/XP3A_7") (class "Default")
      (node (ref "U1") (pin "Y7") (pinfunction "IO_L17P_3_Y7") (pintype "bidirectional"))
    )
    (net (code "379") (name "/XP3A_8") (class "Default")
      (node (ref "U1") (pin "AD2") (pinfunction "IO_L35P_M3DQ10_3_AD2") (pintype "bidirectional"))
    )
    (net (code "380") (name "/XP3A_9") (class "Default")
      (node (ref "U1") (pin "AB9") (pinfunction "IO_L60N_2_AB9") (pintype "bidirectional"))
    )
    (net (code "381") (name "/XP3A_10") (class "Default")
      (node (ref "U1") (pin "AC1") (pinfunction "IO_L36N_M3DQ9_3_AC1") (pintype "bidirectional"))
    )
    (net (code "382") (name "/XP3A_11") (class "Default")
      (node (ref "U1") (pin "Y8") (pinfunction "IO_L3N_3_Y8") (pintype "bidirectional"))
    )
    (net (code "383") (name "/XP3A_12") (class "Default")
      (node (ref "U1") (pin "AA6") (pinfunction "IO_L8N_3_AA6") (pintype "bidirectional"))
    )
    (net (code "384") (name "/XP3A_13") (class "Default")
      (node (ref "U1") (pin "V3") (pinfunction "IO_L44N_GCLK20_M3A6_3_V3") (pintype "bidirectional"))
    )
    (net (code "385") (name "/XP3A_14") (class "Default")
      (node (ref "U1") (pin "AA10") (pinfunction "IO_L1P_3_AA10") (pintype "bidirectional"))
    )
    (net (code "386") (name "/XP3A_15") (class "Default")
      (node (ref "U1") (pin "V8") (pinfunction "IO_L21P_3_V8") (pintype "bidirectional"))
    )
    (net (code "387") (name "/XP3A_16") (class "Default")
      (node (ref "U1") (pin "W5") (pinfunction "IO_L43P_GCLK23_M3RASN_3_W5") (pintype "bidirectional"))
    )
    (net (code "388") (name "/XP3A_17") (class "Default")
      (node (ref "U1") (pin "W10") (pinfunction "IO_L11P_3_W10") (pintype "bidirectional"))
    )
    (net (code "389") (name "/XP3A_18") (class "Default")
      (node (ref "U1") (pin "U5") (pinfunction "IO_L46P_M3CLK_3_U5") (pintype "bidirectional"))
    )
    (net (code "390") (name "/XP3A_20") (class "Default")
      (node (ref "U1") (pin "T9") (pinfunction "IO_L15P_3_T9") (pintype "bidirectional"))
    )
    (net (code "391") (name "/XP3A_21") (class "Default")
      (node (ref "U1") (pin "N9") (pinfunction "IO_L25N_3_N9") (pintype "bidirectional"))
    )
    (net (code "392") (name "/XP3A_23") (class "Default")
      (node (ref "U1") (pin "N8") (pinfunction "IO_L31P_3_N8") (pintype "bidirectional"))
    )
    (net (code "393") (name "/XP3A_24") (class "Default")
      (node (ref "U1") (pin "N7") (pinfunction "IO_L31N_VREF_3_N7") (pintype "bidirectional"))
    )
    (net (code "394") (name "/XP3A_25") (class "Default")
      (node (ref "U1") (pin "R3") (pinfunction "IO_L51P_M3A10_3_R3") (pintype "bidirectional"))
    )
    (net (code "395") (name "/XP3A_26") (class "Default")
      (node (ref "U1") (pin "M7") (pinfunction "IO_L57P_3_M7") (pintype "bidirectional"))
    )
    (net (code "396") (name "/XP3A_27") (class "Default")
      (node (ref "U1") (pin "M2") (pinfunction "IO_L59P_M4DQ14_4_M2") (pintype "bidirectional"))
    )
    (net (code "397") (name "/XP3A_28") (class "Default")
      (node (ref "U1") (pin "K1") (pinfunction "IO_L61N_M4UDQSN_4_K1") (pintype "bidirectional"))
    )
    (net (code "398") (name "/XP3A_29") (class "Default")
      (node (ref "U1") (pin "L10") (pinfunction "IO_L7N_0_L10") (pintype "bidirectional"))
    )
    (net (code "399") (name "/XP3A_30") (class "Default")
      (node (ref "U1") (pin "K11") (pinfunction "IO_L11N_0_K11") (pintype "bidirectional"))
    )
    (net (code "400") (name "/XP3A_31") (class "Default")
      (node (ref "U1") (pin "K10") (pinfunction "IO_L9P_0_K10") (pintype "bidirectional"))
    )
    (net (code "401") (name "/XP3A_32") (class "Default")
      (node (ref "U1") (pin "J8") (pinfunction "IO_L3P_0_J8") (pintype "bidirectional"))
    )
    (net (code "402") (name "/XP3A_33") (class "Default")
      (node (ref "U1") (pin "J10") (pinfunction "IO_L9N_0_J10") (pintype "bidirectional"))
    )
    (net (code "403") (name "/XP3A_34") (class "Default")
      (node (ref "U1") (pin "H7") (pinfunction "IO_L5P_0_H7") (pintype "bidirectional"))
    )
    (net (code "404") (name "/XP3A_35") (class "Default")
      (node (ref "U1") (pin "H8") (pinfunction "IO_L3N_0_H8") (pintype "bidirectional"))
    )
    (net (code "405") (name "/XP3A_36") (class "Default")
      (node (ref "U1") (pin "K12") (pinfunction "IO_L15N_0_K12") (pintype "bidirectional"))
    )
    (net (code "406") (name "/XP3A_37") (class "Default")
      (node (ref "U1") (pin "G5") (pinfunction "IO_L81P_M4RESET_4_G5") (pintype "bidirectional"))
    )
    (net (code "407") (name "/XP3A_38") (class "Default")
      (node (ref "U1") (pin "G7") (pinfunction "IO_L5N_0_G7") (pintype "bidirectional"))
    )
    (net (code "409") (name "/XP3B_3") (class "Default")
      (node (ref "U1") (pin "AE3") (pinfunction "IO_L30P_3_AE3") (pintype "bidirectional"))
    )
    (net (code "410") (name "/XP3B_4") (class "Default")
      (node (ref "U1") (pin "AE5") (pinfunction "IO_L6P_3_AE5") (pintype "bidirectional"))
    )
    (net (code "411") (name "/XP3B_5") (class "Default")
      (node (ref "U1") (pin "AD6") (pinfunction "IO_L9N_3_AD6") (pintype "bidirectional"))
    )
    (net (code "412") (name "/XP3B_6") (class "Default")
      (node (ref "U1") (pin "AE1") (pinfunction "IO_L30N_3_AE1") (pintype "bidirectional"))
    )
    (net (code "413") (name "/XP3B_7") (class "Default")
      (node (ref "U1") (pin "AC5") (pinfunction "IO_L32P_M3DQ14_3_AC5") (pintype "bidirectional"))
    )
    (net (code "414") (name "/XP3B_8") (class "Default")
      (node (ref "U1") (pin "AB6") (pinfunction "IO_L12N_3_AB6") (pintype "bidirectional"))
    )
    (net (code "415") (name "/XP3B_9") (class "Default")
      (node (ref "U1") (pin "AA5") (pinfunction "IO_L39P_M3LDQS_3_AA5") (pintype "bidirectional"))
    )
    (net (code "416") (name "/XP3B_10") (class "Default")
      (node (ref "U1") (pin "Y6") (pinfunction "IO_L17N_VREF_3_Y6") (pintype "bidirectional"))
    )
    (net (code "417") (name "/XP3B_11") (class "Default")
      (node (ref "U1") (pin "V4") (pinfunction "IO_L44P_GCLK21_M3A5_3_V4") (pintype "bidirectional"))
    )
    (net (code "418") (name "/XP3B_12") (class "Default")
      (node (ref "U1") (pin "U3") (pinfunction "IO_L47P_M3A0_3_U3") (pintype "bidirectional"))
    )
    (net (code "419") (name "/XP3B_13") (class "Default")
      (node (ref "U1") (pin "W6") (pinfunction "IO_L13N_3_W6") (pintype "bidirectional"))
    )
    (net (code "420") (name "/XP3B_14") (class "Default")
      (node (ref "U1") (pin "U7") (pinfunction "IO_L29P_3_U7") (pintype "bidirectional"))
    )
    (net (code "421") (name "/XP3B_15") (class "Default")
      (node (ref "U1") (pin "U6") (pinfunction "IO_L29N_3_U6") (pintype "bidirectional"))
    )
    (net (code "422") (name "/XP3B_16") (class "Default")
      (node (ref "U1") (pin "T6") (pinfunction "IO_L7N_3_T6") (pintype "bidirectional"))
    )
    (net (code "423") (name "/XP3B_17") (class "Default")
      (node (ref "U1") (pin "U4") (pinfunction "IO_L46N_M3CLKN_3_U4") (pintype "bidirectional"))
    )
    (net (code "424") (name "/XP3B_18") (class "Default")
      (node (ref "U1") (pin "R5") (pinfunction "IO_L50P_M3WE_3_R5") (pintype "bidirectional"))
    )
    (net (code "425") (name "/XP3B_19") (class "Default")
      (node (ref "U1") (pin "R4") (pinfunction "IO_L50N_M3BA2_3_R4") (pintype "bidirectional"))
    )
    (net (code "426") (name "/XP3B_20") (class "Default")
      (node (ref "U1") (pin "T7") (pinfunction "IO_L7P_3_T7") (pintype "bidirectional"))
    )
    (net (code "427") (name "/XP3B_21") (class "Default")
      (node (ref "U1") (pin "T8") (pinfunction "IO_L15N_3_T8") (pintype "bidirectional"))
    )
    (net (code "428") (name "/XP3B_22") (class "Default")
      (node (ref "U1") (pin "P3") (pinfunction "IO_L52N_M3A9_3_P3") (pintype "bidirectional"))
    )
    (net (code "429") (name "/XP3B_23") (class "Default")
      (node (ref "U1") (pin "P4") (pinfunction "IO_L52P_M3A8_3_P4") (pintype "bidirectional"))
    )
    (net (code "430") (name "/XP3B_24") (class "Default")
      (node (ref "U1") (pin "N3") (pinfunction "IO_L55P_M3A13_3_N3") (pintype "bidirectional"))
    )
    (net (code "431") (name "/XP3B_25") (class "Default")
      (node (ref "U1") (pin "R6") (pinfunction "IO_L27N_3_R6") (pintype "bidirectional"))
    )
    (net (code "432") (name "/XP3B_26") (class "Default")
      (node (ref "U1") (pin "M3") (pinfunction "IO_L63N_M4DQ9_4_M3") (pintype "bidirectional"))
    )
    (net (code "433") (name "/XP3B_27") (class "Default")
      (node (ref "U1") (pin "R1") (pinfunction "IO_L51N_M3A4_3_R1") (pintype "bidirectional"))
    )
    (net (code "434") (name "/XP3B_28") (class "Default")
      (node (ref "U1") (pin "N4") (pinfunction "IO_L53N_M3A12_3_N4") (pintype "bidirectional"))
    )
    (net (code "435") (name "/XP3B_29") (class "Default")
      (node (ref "U1") (pin "P7") (pinfunction "IO_L56P_3_P7") (pintype "bidirectional"))
    )
    (net (code "436") (name "/XP3B_30") (class "Default")
      (node (ref "U1") (pin "P6") (pinfunction "IO_L56N_3_P6") (pintype "bidirectional"))
    )
    (net (code "437") (name "/XP3B_31") (class "Default")
      (node (ref "U1") (pin "K2") (pinfunction "IO_L61P_M4UDQS_4_K2") (pintype "bidirectional"))
    )
    (net (code "438") (name "/XP3B_32") (class "Default")
      (node (ref "U1") (pin "L6") (pinfunction "IO_L58N_VREF_4_L6") (pintype "bidirectional"))
    )
    (net (code "439") (name "/XP3B_33") (class "Default")
      (node (ref "U1") (pin "L5") (pinfunction "IO_L62P_M4DQ10_4_L5") (pintype "bidirectional"))
    )
    (net (code "440") (name "/XP3B_34") (class "Default")
      (node (ref "U1") (pin "J6") (pinfunction "IO_L83P_4_J6") (pintype "bidirectional"))
    )
    (net (code "441") (name "/XP3B_35") (class "Default")
      (node (ref "U1") (pin "J5") (pinfunction "IO_L66P_M4LDQS_4_J5") (pintype "bidirectional"))
    )
    (net (code "442") (name "/XP3B_36") (class "Default")
      (node (ref "U1") (pin "H6") (pinfunction "IO_L83N_VREF_4_H6") (pintype "bidirectional"))
    )
    (net (code "443") (name "/XP3B_37") (class "Default")
      (node (ref "U1") (pin "F3") (pinfunction "IO_L77N_M4BA2_4_F3") (pintype "bidirectional"))
    )
    (net (code "444") (name "/XP3B_38") (class "Default")
      (node (ref "U1") (pin "E3") (pinfunction "IO_L73P_M4CLK_4_E3") (pintype "bidirectional"))
    )
    (net (code "446") (name "/XP3C_3") (class "Default")
      (node (ref "U1") (pin "AC4") (pinfunction "IO_L32N_M3DQ15_3_AC4") (pintype "bidirectional"))
    )
    (net (code "447") (name "/XP3C_4") (class "Default")
      (node (ref "U1") (pin "AC3") (pinfunction "IO_L36P_M3DQ8_3_AC3") (pintype "bidirectional"))
    )
    (net (code "448") (name "/XP3C_5") (class "Default")
      (node (ref "U1") (pin "AB3") (pinfunction "IO_L34N_M3UDQSN_3_AB3") (pintype "bidirectional"))
    )
    (net (code "449") (name "/XP3C_6") (class "Default")
      (node (ref "U1") (pin "AB4") (pinfunction "IO_L34P_M3UDQS_3_AB4") (pintype "bidirectional"))
    )
    (net (code "450") (name "/XP3C_7") (class "Default")
      (node (ref "U1") (pin "AA4") (pinfunction "IO_L39N_M3LDQSN_3_AA4") (pintype "bidirectional"))
    )
    (net (code "451") (name "/XP3C_8") (class "Default")
      (node (ref "U1") (pin "AC6") (pinfunction "IO_L9P_3_AC6") (pintype "bidirectional"))
    )
    (net (code "452") (name "/XP3C_9") (class "Default")
      (node (ref "U1") (pin "W3") (pinfunction "IO_L40P_M3DQ6_3_W3") (pintype "bidirectional"))
    )
    (net (code "453") (name "/XP3C_10") (class "Default")
      (node (ref "U1") (pin "AA9") (pinfunction "IO_L1N_VREF_3_AA9") (pintype "bidirectional"))
    )
    (net (code "454") (name "/XP3C_11") (class "Default")
      (node (ref "U1") (pin "W7") (pinfunction "IO_L13P_3_W7") (pintype "bidirectional"))
    )
    (net (code "455") (name "/XP3C_12") (class "Default")
      (node (ref "U1") (pin "AB2") (pinfunction "IO_L42P_GCLK25_TRDY2_M3UDM_3_AB2") (pintype "bidirectional"))
    )
    (net (code "456") (name "/XP3C_13") (class "Default")
      (node (ref "U1") (pin "V7") (pinfunction "IO_L21N_3_V7") (pintype "bidirectional"))
    )
    (net (code "457") (name "/XP3C_14") (class "Default")
      (node (ref "U1") (pin "W1") (pinfunction "IO_L40N_M3DQ7_3_W1") (pintype "bidirectional"))
    )
    (net (code "458") (name "/XP3C_15") (class "Default")
      (node (ref "U1") (pin "W4") (pinfunction "IO_L43N_GCLK22_IRDY2_M3CASN_3_W4") (pintype "bidirectional"))
    )
    (net (code "459") (name "/XP3C_16") (class "Default")
      (node (ref "U1") (pin "V9") (pinfunction "IO_L23N_3_V9") (pintype "bidirectional"))
    )
    (net (code "460") (name "/XP3C_17") (class "Default")
      (node (ref "U1") (pin "R7") (pinfunction "IO_L27P_3_R7") (pintype "bidirectional"))
    )
    (net (code "461") (name "/XP3C_18") (class "Default")
      (node (ref "U1") (pin "V1") (pinfunction "IO_L45N_M3ODT_3_V1") (pintype "bidirectional"))
    )
    (net (code "462") (name "/XP3C_19") (class "Default")
      (node (ref "U1") (pin "T3") (pinfunction "IO_L48N_M3BA1_3_T3") (pintype "bidirectional"))
    )
    (net (code "463") (name "/XP3C_22") (class "Default")
      (node (ref "U1") (pin "T2") (pinfunction "IO_L49P_M3A7_3_T2") (pintype "bidirectional"))
    )
    (net (code "464") (name "/XP3C_23") (class "Default")
      (node (ref "U1") (pin "V10") (pinfunction "IO_L23P_3_V10") (pintype "bidirectional"))
    )
    (net (code "465") (name "/XP3C_24") (class "Default")
      (node (ref "U1") (pin "N1") (pinfunction "IO_L55N_M3A14_3_N1") (pintype "bidirectional"))
    )
    (net (code "466") (name "/XP3C_25") (class "Default")
      (node (ref "U1") (pin "M1") (pinfunction "IO_L59N_M4DQ15_4_M1") (pintype "bidirectional"))
    )
    (net (code "467") (name "/XP3C_26") (class "Default")
      (node (ref "U1") (pin "L1") (pinfunction "IO_L60N_M4DQ13_4_L1") (pintype "bidirectional"))
    )
    (net (code "468") (name "/XP3C_27") (class "Default")
      (node (ref "U1") (pin "N5") (pinfunction "IO_L53P_M3CKE_3_N5") (pintype "bidirectional"))
    )
    (net (code "469") (name "/XP3C_28") (class "Default")
      (node (ref "U1") (pin "L4") (pinfunction "IO_L62N_M4DQ11_4_L4") (pintype "bidirectional"))
    )
    (net (code "470") (name "/XP3C_29") (class "Default")
      (node (ref "U1") (pin "K3") (pinfunction "IO_L69N_M4LDM_4_K3") (pintype "bidirectional"))
    )
    (net (code "471") (name "/XP3C_30") (class "Default")
      (node (ref "U1") (pin "K4") (pinfunction "IO_L69P_M4UDM_4_K4") (pintype "bidirectional"))
    )
    (net (code "472") (name "/XP3C_31") (class "Default")
      (node (ref "U1") (pin "J3") (pinfunction "IO_L65P_M4DQ2_4_J3") (pintype "bidirectional"))
    )
    (net (code "473") (name "/XP3C_32") (class "Default")
      (node (ref "U1") (pin "J4") (pinfunction "IO_L66N_M4LDQSN_4_J4") (pintype "bidirectional"))
    )
    (net (code "474") (name "/XP3C_33") (class "Default")
      (node (ref "U1") (pin "G1") (pinfunction "IO_L68N_M4DQ5_4_G1") (pintype "bidirectional"))
    )
    (net (code "475") (name "/XP3C_34") (class "Default")
      (node (ref "U1") (pin "H4") (pinfunction "IO_L64P_M4DQ0_4_H4") (pintype "bidirectional"))
    )
    (net (code "476") (name "/XP3C_35") (class "Default")
      (node (ref "U1") (pin "G3") (pinfunction "IO_L68P_M4DQ4_4_G3") (pintype "bidirectional"))
    )
    (net (code "477") (name "/XP3C_36") (class "Default")
      (node (ref "U1") (pin "E1") (pinfunction "IO_L73N_M4CLKN_4_E1") (pintype "bidirectional"))
    )
    (net (code "478") (name "/XP3C_37") (class "Default")
      (node (ref "U1") (pin "C1") (pinfunction "IO_L70P_M4RASN_4_C1") (pintype "bidirectional"))
    )
    (net (code "479") (name "/XP3C_38") (class "Default")
      (node (ref "U1") (pin "B1") (pinfunction "IO_L70N_M4CASN_4_B1") (pintype "bidirectional"))
    )
    (net (code "481") (name "/XP3D_3") (class "Default")
      (node (ref "U1") (pin "AE6") (pinfunction "IO_L4P_3_AE6") (pintype "bidirectional"))
    )
    (net (code "482") (name "/XP3D_4") (class "Default")
      (node (ref "U1") (pin "AG3") (pinfunction "IO_L20N_3_AG3") (pintype "bidirectional"))
    )
    (net (code "483") (name "/XP3D_5") (class "Default")
      (node (ref "U1") (pin "AD4") (pinfunction "IO_L33P_M3DQ12_3_AD4") (pintype "bidirectional"))
    )
    (net (code "484") (name "/XP3D_6") (class "Default")
      (node (ref "U1") (pin "AG1") (pinfunction "IO_L28N_3_AG1") (pintype "bidirectional"))
    )
    (net (code "485") (name "/XP3D_7") (class "Default")
      (node (ref "U1") (pin "AF2") (pinfunction "IO_L26P_3_AF2") (pintype "bidirectional"))
    )
    (net (code "486") (name "/XP3D_8") (class "Default")
      (node (ref "U1") (pin "AF1") (pinfunction "IO_L28P_3_AF1") (pintype "bidirectional"))
    )
    (net (code "487") (name "/XP3D_9") (class "Default")
      (node (ref "U1") (pin "W12") (pinfunction "IO_L56P_2_W12") (pintype "bidirectional"))
    )
    (net (code "488") (name "/XP3D_10") (class "Default")
      (node (ref "U1") (pin "M15") (pinfunction "IO_L25P_0_M15") (pintype "bidirectional"))
    )
    (net (code "489") (name "/XP3D_11") (class "Default")
      (node (ref "U1") (pin "AD1") (pinfunction "IO_L35N_M3DQ11_3_AD1") (pintype "bidirectional"))
    )
    (net (code "490") (name "/XP3D_12") (class "Default")
      (node (ref "U1") (pin "Y3") (pinfunction "IO_L37N_M3DQ1_3_Y3") (pintype "bidirectional"))
    )
    (net (code "491") (name "/XP3D_13") (class "Default")
      (node (ref "U1") (pin "AB1") (pinfunction "IO_L42N_GCLK24_M3LDM_3_AB1") (pintype "bidirectional"))
    )
    (net (code "492") (name "/XP3D_14") (class "Default")
      (node (ref "U1") (pin "AA1") (pinfunction "IO_L41N_GCLK26_M3DQ5_3_AA1") (pintype "bidirectional"))
    )
    (net (code "493") (name "/XP3D_15") (class "Default")
      (node (ref "U1") (pin "Y2") (pinfunction "IO_L38P_M3DQ2_3_Y2") (pintype "bidirectional"))
    )
    (net (code "494") (name "/XP3D_16") (class "Default")
      (node (ref "U1") (pin "Y1") (pinfunction "IO_L38N_M3DQ3_3_Y1") (pintype "bidirectional"))
    )
    (net (code "495") (name "/XP3D_17") (class "Default")
      (node (ref "U1") (pin "T4") (pinfunction "IO_L48P_M3BA0_3_T4") (pintype "bidirectional"))
    )
    (net (code "496") (name "/XP3D_18") (class "Default")
      (node (ref "U1") (pin "V2") (pinfunction "IO_L45P_M3A3_3_V2") (pintype "bidirectional"))
    )
    (net (code "497") (name "/XP3D_19") (class "Default")
      (node (ref "U1") (pin "U1") (pinfunction "IO_L47N_M3A1_3_U1") (pintype "bidirectional"))
    )
    (net (code "498") (name "/XP3D_22") (class "Default")
      (node (ref "U1") (pin "T1") (pinfunction "IO_L49N_M3A2_3_T1") (pintype "bidirectional"))
    )
    (net (code "499") (name "/XP3D_23") (class "Default")
      (node (ref "U1") (pin "P1") (pinfunction "IO_L54N_M3A11_3_P1") (pintype "bidirectional"))
    )
    (net (code "500") (name "/XP3D_24") (class "Default")
      (node (ref "U1") (pin "P2") (pinfunction "IO_L54P_M3RESET_3_P2") (pintype "bidirectional"))
    )
    (net (code "501") (name "/XP3D_25") (class "Default")
      (node (ref "U1") (pin "M6") (pinfunction "IO_L57N_VREF_3_M6") (pintype "bidirectional"))
    )
    (net (code "502") (name "/XP3D_26") (class "Default")
      (node (ref "U1") (pin "L7") (pinfunction "IO_L58P_4_L7") (pintype "bidirectional"))
    )
    (net (code "503") (name "/XP3D_27") (class "Default")
      (node (ref "U1") (pin "L3") (pinfunction "IO_L60P_M4DQ12_4_L3") (pintype "bidirectional"))
    )
    (net (code "504") (name "/XP3D_28") (class "Default")
      (node (ref "U1") (pin "M4") (pinfunction "IO_L63P_M4DQ8_4_M4") (pintype "bidirectional"))
    )
    (net (code "505") (name "/XP3D_29") (class "Default")
      (node (ref "U1") (pin "J1") (pinfunction "IO_L65N_M4DQ3_4_J1") (pintype "bidirectional"))
    )
    (net (code "506") (name "/XP3D_30") (class "Default")
      (node (ref "U1") (pin "H1") (pinfunction "IO_L67N_M4DQ7_4_H1") (pintype "bidirectional"))
    )
    (net (code "507") (name "/XP3D_31") (class "Default")
      (node (ref "U1") (pin "H2") (pinfunction "IO_L67P_M4DQ6_4_H2") (pintype "bidirectional"))
    )
    (net (code "508") (name "/XP3D_32") (class "Default")
      (node (ref "U1") (pin "H3") (pinfunction "IO_L64N_M4DQ1_4_H3") (pintype "bidirectional"))
    )
    (net (code "509") (name "/XP3D_33") (class "Default")
      (node (ref "U1") (pin "F1") (pinfunction "IO_L71N_M4A6_4_F1") (pintype "bidirectional"))
    )
    (net (code "510") (name "/XP3D_34") (class "Default")
      (node (ref "U1") (pin "F2") (pinfunction "IO_L71P_M4A5_4_F2") (pintype "bidirectional"))
    )
    (net (code "511") (name "/XP3D_35") (class "Default")
      (node (ref "U1") (pin "G4") (pinfunction "IO_L81N_M4A11_4_G4") (pintype "bidirectional"))
    )
    (net (code "512") (name "/XP3D_36") (class "Default")
      (node (ref "U1") (pin "D1") (pinfunction "IO_L75N_M4BA1_4_D1") (pintype "bidirectional"))
    )
    (net (code "513") (name "/XP3D_37") (class "Default")
      (node (ref "U1") (pin "D2") (pinfunction "IO_L75P_M4BA0_4_D2") (pintype "bidirectional"))
    )
    (net (code "514") (name "/XP3D_38") (class "Default")
      (node (ref "U1") (pin "F4") (pinfunction "IO_L77P_M4WE_4_F4") (pintype "bidirectional"))
    )
    (net (code "515") (name "/XP4A_3") (class "Default")
      (node (ref "U1") (pin "J30") (pinfunction "IO_L18N_M5LDQSN_5_J30") (pintype "bidirectional"))
    )
    (net (code "516") (name "/XP4A_4") (class "Default")
      (node (ref "U1") (pin "E28") (pinfunction "IO_L11N_M5CLKN_5_E28") (pintype "bidirectional"))
    )
    (net (code "517") (name "/XP4A_5") (class "Default")
      (node (ref "U1") (pin "E30") (pinfunction "IO_L12N_M5ODT_5_E30") (pintype "bidirectional"))
    )
    (net (code "518") (name "/XP4A_6") (class "Default")
      (node (ref "U1") (pin "E26") (pinfunction "IO_L7P_M5WE_5_E26") (pintype "bidirectional"))
    )
    (net (code "519") (name "/XP4A_7") (class "Default")
      (node (ref "U1") (pin "E29") (pinfunction "IO_L12P_M5A3_5_E29") (pintype "bidirectional"))
    )
    (net (code "520") (name "/XP4A_8") (class "Default")
      (node (ref "U1") (pin "C24") (pinfunction "IO_L64N_SCP4_0_C24") (pintype "bidirectional"))
    )
    (net (code "521") (name "/XP4A_9") (class "Default")
      (node (ref "U1") (pin "E23") (pinfunction "IO_L60N_0_E23") (pintype "bidirectional"))
    )
    (net (code "522") (name "/XP4A_11") (class "Default")
      (node (ref "U1") (pin "B25") (pinfunction "IO_L63P_SCP7_0_B25") (pintype "bidirectional"))
    )
    (net (code "523") (name "/XP4A_12") (class "Default")
      (node (ref "U1") (pin "F20") (pinfunction "IO_L54N_0_F20") (pintype "bidirectional"))
    )
    (net (code "524") (name "/XP4A_13") (class "Default")
      (node (ref "U1") (pin "A25") (pinfunction "IO_L63N_SCP6_0_A25") (pintype "bidirectional"))
    )
    (net (code "525") (name "/XP4A_14") (class "Default")
      (node (ref "U1") (pin "J20") (pinfunction "IO_L55N_0_J20") (pintype "bidirectional"))
    )
    (net (code "526") (name "/XP4A_15") (class "Default")
      (node (ref "U1") (pin "H22") (pinfunction "IO_L65N_SCP2_0_H22") (pintype "bidirectional"))
    )
    (net (code "527") (name "/XP4A_16") (class "Default")
      (node (ref "U1") (pin "E21") (pinfunction "IO_L56N_0_E21") (pintype "bidirectional"))
    )
    (net (code "528") (name "/XP4A_17") (class "Default")
      (node (ref "U1") (pin "J22") (pinfunction "IO_L65P_SCP3_0_J22") (pintype "bidirectional"))
    )
    (net (code "529") (name "/XP4A_18") (class "Default")
      (node (ref "U1") (pin "E19") (pinfunction "IO_L50N_0_E19") (pintype "bidirectional"))
    )
    (net (code "530") (name "/XP4A_19") (class "Default")
      (node (ref "U1") (pin "F17") (pinfunction "IO_L48P_0_F17") (pintype "bidirectional"))
    )
    (net (code "531") (name "/XP4A_22") (class "Default")
      (node (ref "U1") (pin "C16") (pinfunction "IO_L36P_GCLK15_0_C16") (pintype "bidirectional"))
    )
    (net (code "532") (name "/XP4A_23") (class "Default")
      (node (ref "U1") (pin "A16") (pinfunction "IO_L36N_GCLK14_0_A16") (pintype "bidirectional"))
    )
    (net (code "533") (name "/XP4A_24") (class "Default")
      (node (ref "U1") (pin "E13") (pinfunction "IO_L24N_0_E13") (pintype "bidirectional"))
    )
    (net (code "534") (name "/XP4A_25") (class "Default")
      (node (ref "U1") (pin "A15") (pinfunction "IO_L35N_GCLK16_0_A15") (pintype "bidirectional"))
    )
    (net (code "535") (name "/XP4A_26") (class "Default")
      (node (ref "U1") (pin "F10") (pinfunction "IO_L14N_0_F10") (pintype "bidirectional"))
    )
    (net (code "536") (name "/XP4A_27") (class "Default")
      (node (ref "U1") (pin "L19") (pinfunction "IO_L51N_0_L19") (pintype "bidirectional"))
    )
    (net (code "537") (name "/XP4A_28") (class "Default")
      (node (ref "U1") (pin "F14") (pinfunction "IO_L26N_0_F14") (pintype "bidirectional"))
    )
    (net (code "538") (name "/XP4A_29") (class "Default")
      (node (ref "U1") (pin "J13") (pinfunction "IO_L19P_0_J13") (pintype "bidirectional"))
    )
    (net (code "539") (name "/XP4A_30") (class "Default")
      (node (ref "U1") (pin "L12") (pinfunction "IO_L15P_0_L12") (pintype "bidirectional"))
    )
    (net (code "540") (name "/XP4A_31") (class "Default")
      (node (ref "U1") (pin "A7") (pinfunction "IO_L13N_0_A7") (pintype "bidirectional"))
    )
    (net (code "541") (name "/XP4A_32") (class "Default")
      (node (ref "U1") (pin "B7") (pinfunction "IO_L13P_0_B7") (pintype "bidirectional"))
    )
    (net (code "542") (name "/XP4A_33") (class "Default")
      (node (ref "U1") (pin "A6") (pinfunction "IO_L8N_VREF_0_A6") (pintype "bidirectional"))
    )
    (net (code "543") (name "/XP4A_34") (class "Default")
      (node (ref "U1") (pin "A5") (pinfunction "IO_L82N_M4A14_4_A5") (pintype "bidirectional"))
    )
    (net (code "544") (name "/XP4A_35") (class "Default")
      (node (ref "U1") (pin "B5") (pinfunction "IO_L82P_M4A13_4_B5") (pintype "bidirectional"))
    )
    (net (code "545") (name "/XP4A_36") (class "Default")
      (node (ref "U1") (pin "A3") (pinfunction "IO_L76N_M4A2_4_A3") (pintype "bidirectional"))
    )
    (net (code "546") (name "/XP4A_37") (class "Default")
      (node (ref "U1") (pin "E4") (pinfunction "IO_L72N_M4ODT_4_E4") (pintype "bidirectional"))
    )
    (net (code "547") (name "/XP4A_38") (class "Default")
      (node (ref "U1") (pin "D3") (pinfunction "IO_L74N_M4A1_4_D3") (pintype "bidirectional"))
    )
    (net (code "549") (name "/XP4B_3") (class "Default")
      (node (ref "U1") (pin "K30") (pinfunction "IO_L23N_M5UDQSN_5_K30") (pintype "bidirectional"))
    )
    (net (code "550") (name "/XP4B_4") (class "Default")
      (node (ref "U1") (pin "F27") (pinfunction "IO_L6N_M5A4_5_F27") (pintype "bidirectional"))
    )
    (net (code "551") (name "/XP4B_5") (class "Default")
      (node (ref "U1") (pin "D30") (pinfunction "IO_L10N_M5A1_5_D30") (pintype "bidirectional"))
    )
    (net (code "552") (name "/XP4B_6") (class "Default")
      (node (ref "U1") (pin "C27") (pinfunction "IO_L9N_M5BA1_5_C27") (pintype "bidirectional"))
    )
    (net (code "553") (name "/XP4B_7") (class "Default")
      (node (ref "U1") (pin "B29") (pinfunction "IO_L4P_M5CKE_5_B29") (pintype "bidirectional"))
    )
    (net (code "554") (name "/XP4B_8") (class "Default")
      (node (ref "U1") (pin "E25") (pinfunction "IO_L66P_SCP1_0_E25") (pintype "bidirectional"))
    )
    (net (code "555") (name "/XP4B_9") (class "Default")
      (node (ref "U1") (pin "F28") (pinfunction "IO_L17P_M5DQ6_5_F28") (pintype "bidirectional"))
    )
    (net (code "556") (name "/XP4B_10") (class "Default")
      (node (ref "U1") (pin "E27") (pinfunction "IO_L11P_M5CLK_5_E27") (pintype "bidirectional"))
    )
    (net (code "557") (name "/XP4B_11") (class "Default")
      (node (ref "U1") (pin "F22") (pinfunction "IO_L58N_0_F22") (pintype "bidirectional"))
    )
    (net (code "558") (name "/XP4B_12") (class "Default")
      (node (ref "U1") (pin "F21") (pinfunction "IO_L56P_0_F21") (pintype "bidirectional"))
    )
    (net (code "559") (name "/XP4B_13") (class "Default")
      (node (ref "U1") (pin "D24") (pinfunction "IO_L64P_SCP5_0_D24") (pintype "bidirectional"))
    )
    (net (code "560") (name "/XP4B_14") (class "Default")
      (node (ref "U1") (pin "F18") (pinfunction "IO_L46N_0_F18") (pintype "bidirectional"))
    )
    (net (code "561") (name "/XP4B_15") (class "Default")
      (node (ref "U1") (pin "E17") (pinfunction "IO_L48N_0_E17") (pintype "bidirectional"))
    )
    (net (code "562") (name "/XP4B_16") (class "Default")
      (node (ref "U1") (pin "G22") (pinfunction "IO_L58P_0_G22") (pintype "bidirectional"))
    )
    (net (code "563") (name "/XP4B_17") (class "Default")
      (node (ref "U1") (pin "K19") (pinfunction "IO_L49P_0_K19") (pintype "bidirectional"))
    )
    (net (code "564") (name "/XP4B_18") (class "Default")
      (node (ref "U1") (pin "G16") (pinfunction "IO_L45N_0_G16") (pintype "bidirectional"))
    )
    (net (code "565") (name "/XP4B_19") (class "Default")
      (node (ref "U1") (pin "J14") (pinfunction "IO_L32P_0_J14") (pintype "bidirectional"))
    )
    (net (code "566") (name "/XP4B_22") (class "Default")
      (node (ref "U1") (pin "A17") (pinfunction "IO_L38N_VREF_0_A17") (pintype "bidirectional"))
    )
    (net (code "567") (name "/XP4B_23") (class "Default")
      (node (ref "U1") (pin "F19") (pinfunction "IO_L50P_0_F19") (pintype "bidirectional"))
    )
    (net (code "568") (name "/XP4B_24") (class "Default")
      (node (ref "U1") (pin "G12") (pinfunction "IO_L22P_0_G12") (pintype "bidirectional"))
    )
    (net (code "569") (name "/XP4B_25") (class "Default")
      (node (ref "U1") (pin "E11") (pinfunction "IO_L18N_0_E11") (pintype "bidirectional"))
    )
    (net (code "570") (name "/XP4B_26") (class "Default")
      (node (ref "U1") (pin "G9") (pinfunction "IO_L1N_VREF_0_G9") (pintype "bidirectional"))
    )
    (net (code "571") (name "/XP4B_27") (class "Default")
      (node (ref "U1") (pin "C8") (pinfunction "IO_L12N_0_C8") (pintype "bidirectional"))
    )
    (net (code "572") (name "/XP4B_28") (class "Default")
      (node (ref "U1") (pin "D8") (pinfunction "IO_L12P_0_D8") (pintype "bidirectional"))
    )
    (net (code "573") (name "/XP4B_29") (class "Default")
      (node (ref "U1") (pin "D7") (pinfunction "IO_L6N_0_D7") (pintype "bidirectional"))
    )
    (net (code "574") (name "/XP4B_30") (class "Default")
      (node (ref "U1") (pin "C6") (pinfunction "IO_L4N_0_C6") (pintype "bidirectional"))
    )
    (net (code "575") (name "/XP4B_31") (class "Default")
      (node (ref "U1") (pin "D6") (pinfunction "IO_L4P_0_D6") (pintype "bidirectional"))
    )
    (net (code "576") (name "/XP4B_32") (class "Default")
      (node (ref "U1") (pin "C5") (pinfunction "IO_L78N_M4A4_4_C5") (pintype "bidirectional"))
    )
    (net (code "577") (name "/XP4B_33") (class "Default")
      (node (ref "U1") (pin "D5") (pinfunction "IO_L78P_M4A10_4_D5") (pintype "bidirectional"))
    )
    (net (code "578") (name "/XP4B_34") (class "Default")
      (node (ref "U1") (pin "C4") (pinfunction "IO_L80P_M4CKE_4_C4") (pintype "bidirectional"))
    )
    (net (code "579") (name "/XP4B_35") (class "Default")
      (node (ref "U1") (pin "E5") (pinfunction "IO_L72P_M4A3_4_E5") (pintype "bidirectional"))
    )
    (net (code "580") (name "/XP4B_36") (class "Default")
      (node (ref "U1") (pin "B2") (pinfunction "IO_L79P_M4A8_4_B2") (pintype "bidirectional"))
    )
    (net (code "581") (name "/XP4B_37") (class "Default")
      (node (ref "U1") (pin "D4") (pinfunction "IO_L74P_M4A0_4_D4") (pintype "bidirectional"))
    )
    (net (code "582") (name "/XP4B_38") (class "Default")
      (node (ref "U1") (pin "A2") (pinfunction "IO_L79N_M4A9_4_A2") (pintype "bidirectional"))
    )
    (net (code "584") (name "/XP4C_3") (class "Default")
      (node (ref "U1") (pin "H30") (pinfunction "IO_L20N_M5DQ1_5_H30") (pintype "bidirectional"))
    )
    (net (code "585") (name "/XP4C_4") (class "Default")
      (node (ref "U1") (pin "J29") (pinfunction "IO_L18P_M5LDQS_5_J29") (pintype "bidirectional"))
    )
    (net (code "586") (name "/XP4C_5") (class "Default")
      (node (ref "U1") (pin "D27") (pinfunction "IO_L9P_M5BA0_5_D27") (pintype "bidirectional"))
    )
    (net (code "587") (name "/XP4C_6") (class "Default")
      (node (ref "U1") (pin "A28") (pinfunction "IO_L2P_M5A13_5_A28") (pintype "bidirectional"))
    )
    (net (code "588") (name "/XP4C_7") (class "Default")
      (node (ref "U1") (pin "D26") (pinfunction "IO_L7N_M5BA2_5_D26") (pintype "bidirectional"))
    )
    (net (code "589") (name "/XP4C_8") (class "Default")
      (node (ref "U1") (pin "C29") (pinfunction "IO_L8P_M5A7_5_C29") (pintype "bidirectional"))
    )
    (net (code "590") (name "/XP4C_9") (class "Default")
      (node (ref "U1") (pin "A29") (pinfunction "IO_L2N_M5A14_5_A29") (pintype "bidirectional"))
    )
    (net (code "591") (name "/XP4C_10") (class "Default")
      (node (ref "U1") (pin "B27") (pinfunction "IO_L5P_M5A8_5_B27") (pintype "bidirectional"))
    )
    (net (code "592") (name "/XP4C_11") (class "Default")
      (node (ref "U1") (pin "A27") (pinfunction "IO_L5N_M5A9_5_A27") (pintype "bidirectional"))
    )
    (net (code "593") (name "/XP4C_12") (class "Default")
      (node (ref "U1") (pin "F24") (pinfunction "IO_L62P_0_F24") (pintype "bidirectional"))
    )
    (net (code "594") (name "/XP4C_13") (class "Default")
      (node (ref "U1") (pin "E24") (pinfunction "IO_L62N_VREF_0_E24") (pintype "bidirectional"))
    )
    (net (code "595") (name "/XP4C_14") (class "Default")
      (node (ref "U1") (pin "F23") (pinfunction "IO_L60P_0_F23") (pintype "bidirectional"))
    )
    (net (code "596") (name "/XP4C_15") (class "Default")
      (node (ref "U1") (pin "H21") (pinfunction "IO_L61P_0_H21") (pintype "bidirectional"))
    )
    (net (code "597") (name "/XP4C_16") (class "Default")
      (node (ref "U1") (pin "E16") (pinfunction "IO_L37P_GCLK13_0_E16") (pintype "bidirectional"))
    )
    (net (code "598") (name "/XP4C_17") (class "Default")
      (node (ref "U1") (pin "H19") (pinfunction "IO_L52P_0_H19") (pintype "bidirectional"))
    )
    (net (code "599") (name "/XP4C_18") (class "Default")
      (node (ref "U1") (pin "K14") (pinfunction "IO_L23N_0_K14") (pintype "bidirectional"))
    )
    (net (code "600") (name "/XP4C_19") (class "Default")
      (node (ref "U1") (pin "G20") (pinfunction "IO_L54P_0_G20") (pintype "bidirectional"))
    )
    (net (code "601") (name "/XP4C_22") (class "Default")
      (node (ref "U1") (pin "G14") (pinfunction "IO_L26P_0_G14") (pintype "bidirectional"))
    )
    (net (code "602") (name "/XP4C_23") (class "Default")
      (node (ref "U1") (pin "G17") (pinfunction "IO_L44N_0_G17") (pintype "bidirectional"))
    )
    (net (code "603") (name "/XP4C_24") (class "Default")
      (node (ref "U1") (pin "H17") (pinfunction "IO_L44P_0_H17") (pintype "bidirectional"))
    )
    (net (code "604") (name "/XP4C_25") (class "Default")
      (node (ref "U1") (pin "H16") (pinfunction "IO_L45P_0_H16") (pintype "bidirectional"))
    )
    (net (code "605") (name "/XP4C_26") (class "Default")
      (node (ref "U1") (pin "J18") (pinfunction "IO_L53P_0_J18") (pintype "bidirectional"))
    )
    (net (code "606") (name "/XP4C_27") (class "Default")
      (node (ref "U1") (pin "K15") (pinfunction "IO_L25N_0_K15") (pintype "bidirectional"))
    )
    (net (code "607") (name "/XP4C_28") (class "Default")
      (node (ref "U1") (pin "L14") (pinfunction "IO_L23P_0_L14") (pintype "bidirectional"))
    )
    (net (code "608") (name "/XP4C_29") (class "Default")
      (node (ref "U1") (pin "H14") (pinfunction "IO_L32N_0_H14") (pintype "bidirectional"))
    )
    (net (code "609") (name "/XP4C_30") (class "Default")
      (node (ref "U1") (pin "F13") (pinfunction "IO_L24P_0_F13") (pintype "bidirectional"))
    )
    (net (code "610") (name "/XP4C_31") (class "Default")
      (node (ref "U1") (pin "F12") (pinfunction "IO_L22N_0_F12") (pintype "bidirectional"))
    )
    (net (code "611") (name "/XP4C_32") (class "Default")
      (node (ref "U1") (pin "G11") (pinfunction "IO_L20N_0_G11") (pintype "bidirectional"))
    )
    (net (code "612") (name "/XP4C_33") (class "Default")
      (node (ref "U1") (pin "G10") (pinfunction "IO_L14P_0_G10") (pintype "bidirectional"))
    )
    (net (code "613") (name "/XP4C_34") (class "Default")
      (node (ref "U1") (pin "F9") (pinfunction "IO_L16P_0_F9") (pintype "bidirectional"))
    )
    (net (code "614") (name "/XP4C_35") (class "Default")
      (node (ref "U1") (pin "E8") (pinfunction "IO_L10N_0_E8") (pintype "bidirectional"))
    )
    (net (code "615") (name "/XP4C_36") (class "Default")
      (node (ref "U1") (pin "E7") (pinfunction "IO_L6P_0_E7") (pintype "bidirectional"))
    )
    (net (code "616") (name "/XP4C_37") (class "Default")
      (node (ref "U1") (pin "E6") (pinfunction "IO_L2N_0_E6") (pintype "bidirectional"))
    )
    (net (code "617") (name "/XP4C_38") (class "Default")
      (node (ref "U1") (pin "F6") (pinfunction "IO_L2P_0_F6") (pintype "bidirectional"))
    )
    (net (code "619") (name "/XP4D_3") (class "Default")
      (node (ref "U1") (pin "G30") (pinfunction "IO_L19N_M5DQ3_5_G30") (pintype "bidirectional"))
    )
    (net (code "620") (name "/XP4D_4") (class "Default")
      (node (ref "U1") (pin "B30") (pinfunction "IO_L4N_M5A12_5_B30") (pintype "bidirectional"))
    )
    (net (code "621") (name "/XP4D_5") (class "Default")
      (node (ref "U1") (pin "D28") (pinfunction "IO_L10P_M5A0_5_D28") (pintype "bidirectional"))
    )
    (net (code "622") (name "/XP4D_6") (class "Default")
      (node (ref "U1") (pin "C30") (pinfunction "IO_L8N_M5A2_5_C30") (pintype "bidirectional"))
    )
    (net (code "623") (name "/XP4D_7") (class "Default")
      (node (ref "U1") (pin "G29") (pinfunction "IO_L19P_M5DQ2_5_G29") (pintype "bidirectional"))
    )
    (net (code "624") (name "/XP4D_8") (class "Default")
      (node (ref "U1") (pin "A26") (pinfunction "IO_L3N_M5A11_5_A26") (pintype "bidirectional"))
    )
    (net (code "625") (name "/XP4D_9") (class "Default")
      (node (ref "U1") (pin "G27") (pinfunction "IO_L16P_M5DQ4_5_G27") (pintype "bidirectional"))
    )
    (net (code "626") (name "/XP4D_10") (class "Default")
      (node (ref "U1") (pin "F26") (pinfunction "IO_L6P_M5A10_5_F26") (pintype "bidirectional"))
    )
    (net (code "627") (name "/XP4D_11") (class "Default")
      (node (ref "U1") (pin "D25") (pinfunction "IO_L66N_SCP0_0_D25") (pintype "bidirectional"))
    )
    (net (code "628") (name "/XP4D_12") (class "Default")
      (node (ref "U1") (pin "C26") (pinfunction "IO_L3P_M5RESET_5_C26") (pintype "bidirectional"))
    )
    (net (code "629") (name "/XP4D_13") (class "Default")
      (node (ref "U1") (pin "K20") (pinfunction "IO_L55P_0_K20") (pintype "bidirectional"))
    )
    (net (code "630") (name "/XP4D_14") (class "Default")
      (node (ref "U1") (pin "J19") (pinfunction "IO_L49N_0_J19") (pintype "bidirectional"))
    )
    (net (code "631") (name "/XP4D_15") (class "Default")
      (node (ref "U1") (pin "G19") (pinfunction "IO_L52N_0_G19") (pintype "bidirectional"))
    )
    (net (code "632") (name "/XP4D_16") (class "Default")
      (node (ref "U1") (pin "G21") (pinfunction "IO_L61N_0_G21") (pintype "bidirectional"))
    )
    (net (code "633") (name "/XP4D_17") (class "Default")
      (node (ref "U1") (pin "H18") (pinfunction "IO_L53N_0_H18") (pintype "bidirectional"))
    )
    (net (code "634") (name "/XP4D_18") (class "Default")
      (node (ref "U1") (pin "K17") (pinfunction "IO_L43N_0_K17") (pintype "bidirectional"))
    )
    (net (code "635") (name "/XP4D_19") (class "Default")
      (node (ref "U1") (pin "D16") (pinfunction "IO_L37N_GCLK12_0_D16") (pintype "bidirectional"))
    )
    (net (code "636") (name "/XP4D_22") (class "Default")
      (node (ref "U1") (pin "B17") (pinfunction "IO_L38P_0_B17") (pintype "bidirectional"))
    )
    (net (code "637") (name "/XP4D_23") (class "Default")
      (node (ref "U1") (pin "L11") (pinfunction "IO_L11P_0_L11") (pintype "bidirectional"))
    )
    (net (code "638") (name "/XP4D_24") (class "Default")
      (node (ref "U1") (pin "L13") (pinfunction "IO_L21N_0_L13") (pintype "bidirectional"))
    )
    (net (code "639") (name "/XP4D_25") (class "Default")
      (node (ref "U1") (pin "G15") (pinfunction "IO_L34N_GCLK18_0_G15") (pintype "bidirectional"))
    )
    (net (code "640") (name "/XP4D_26") (class "Default")
      (node (ref "U1") (pin "B15") (pinfunction "IO_L35P_GCLK17_0_B15") (pintype "bidirectional"))
    )
    (net (code "641") (name "/XP4D_27") (class "Default")
      (node (ref "U1") (pin "E15") (pinfunction "IO_L33N_0_E15") (pintype "bidirectional"))
    )
    (net (code "642") (name "/XP4D_28") (class "Default")
      (node (ref "U1") (pin "F15") (pinfunction "IO_L33P_0_F15") (pintype "bidirectional"))
    )
    (net (code "643") (name "/XP4D_29") (class "Default")
      (node (ref "U1") (pin "H13") (pinfunction "IO_L19N_0_H13") (pintype "bidirectional"))
    )
    (net (code "644") (name "/XP4D_30") (class "Default")
      (node (ref "U1") (pin "F11") (pinfunction "IO_L18P_0_F11") (pintype "bidirectional"))
    )
    (net (code "645") (name "/XP4D_31") (class "Default")
      (node (ref "U1") (pin "J12") (pinfunction "IO_L17P_0_J12") (pintype "bidirectional"))
    )
    (net (code "646") (name "/XP4D_32") (class "Default")
      (node (ref "U1") (pin "H12") (pinfunction "IO_L17N_0_H12") (pintype "bidirectional"))
    )
    (net (code "647") (name "/XP4D_33") (class "Default")
      (node (ref "U1") (pin "B6") (pinfunction "IO_L8P_0_B6") (pintype "bidirectional"))
    )
    (net (code "648") (name "/XP4D_34") (class "Default")
      (node (ref "U1") (pin "H11") (pinfunction "IO_L20P_0_H11") (pintype "bidirectional"))
    )
    (net (code "649") (name "/XP4D_35") (class "Default")
      (node (ref "U1") (pin "A4") (pinfunction "IO_L80N_M4A12_4_A4") (pintype "bidirectional"))
    )
    (net (code "650") (name "/XP4D_36") (class "Default")
      (node (ref "U1") (pin "E9") (pinfunction "IO_L16N_0_E9") (pintype "bidirectional"))
    )
    (net (code "651") (name "/XP4D_37") (class "Default")
      (node (ref "U1") (pin "B3") (pinfunction "IO_L76P_M4A7_4_B3") (pintype "bidirectional"))
    )
    (net (code "652") (name "/XP4D_38") (class "Default")
      (node (ref "U1") (pin "F8") (pinfunction "IO_L10P_0_F8") (pintype "bidirectional"))
    )
    (net (code "654") (name "/adc_eoc") (class "Default")
      (node (ref "U1") (pin "K28") (pinfunction "IO_L23P_M5UDQS_5_K28") (pintype "bidirectional+no_connect"))
    )
    (net (code "655") (name "/adc_ncs") (class "Default")
      (node (ref "U1") (pin "L24") (pinfunction "IO_L27P_5_L24") (pintype "bidirectional"))
    )
    (net (code "656") (name "/adc_sck") (class "Default")
      (node (ref "U1") (pin "J28") (pinfunction "IO_L15N_M5LDM_5_J28") (pintype "bidirectional+no_connect"))
    )
    (net (code "657") (name "/adc_sdi") (class "Default")
      (node (ref "U1") (pin "L25") (pinfunction "IO_L27N_5_L25") (pintype "bidirectional"))
    )
    (net (code "658") (name "/adc_sdo") (class "Default")
      (node (ref "U1") (pin "F30") (pinfunction "IO_L17N_M5DQ7_5_F30") (pintype "bidirectional+no_connect"))
    )
    (net (code "659") (name "/en_2v5_sfp") (class "Default")
      (node (ref "U1") (pin "L27") (pinfunction "IO_L21P_M5DQ8_5_L27") (pintype "bidirectional"))
    )
    (net (code "660") (name "/mc_sn") (class "Default")
      (node (ref "U1") (pin "K21") (pinfunction "IO_L59N_0_K21") (pintype "bidirectional"))
    )
    (net (code "661") (name "/mez_clock") (class "Default")
      (node (ref "R13") (pin "2") (pinfunction "2_2") (pintype "passive"))
      (node (ref "R14") (pin "1") (pinfunction "1_1") (pintype "passive"))
      (node (ref "U1") (pin "V27") (pinfunction "IO_L40N_GCLK10_M1A6_1_V27") (pintype "bidirectional"))
    )
    (net (code "662") (name "/sda1_3v3") (class "Default")
      (node (ref "U1") (pin "Y11") (pinfunction "IO_L5N_3_Y11") (pintype "bidirectional"))
    )
    (net (code "663") (name "/sda2_3v3") (class "Default")
      (node (ref "U1") (pin "G18") (pinfunction "IO_L46P_0_G18") (pintype "bidirectional"))
    )
    (net (code "664") (name "/sfp_disable") (class "Default")
      (node (ref "U1") (pin "M10") (pinfunction "IO_L7P_0_M10") (pintype "bidirectional+no_connect"))
    )
    (net (code "665") (name "/sfp_i2c_scl") (class "Default")
      (node (ref "U1") (pin "H15") (pinfunction "IO_L34P_GCLK19_0_H15") (pintype "bidirectional"))
    )
    (net (code "666") (name "/sfp_i2c_scl2") (class "Default")
      (node (ref "U1") (pin "M13") (pinfunction "IO_L21P_0_M13") (pintype "bidirectional"))
    )
    (net (code "667") (name "/sfp_i2c_sda") (class "Default")
      (node (ref "U1") (pin "N10") (pinfunction "IO_L25P_3_N10") (pintype "bidirectional"))
    )
    (net (code "668") (name "/sfp_i2c_sda2") (class "Default")
      (node (ref "U1") (pin "Y4") (pinfunction "IO_L37P_M3DQ0_3_Y4") (pintype "bidirectional"))
    )
    (net (code "669") (name "/unused4") (class "Default")
      (node (ref "U1") (pin "L20") (pinfunction "IO_L57N_0_L20") (pintype "bidirectional+no_connect"))
    )
    (net (code "670") (name "GND") (class "Default")
      (node (ref "R14") (pin "2") (pinfunction "2_2") (pintype "passive"))
    )
  )
)
